# Tester.net
KiCad netlist of a schematic drawn in EAGLE
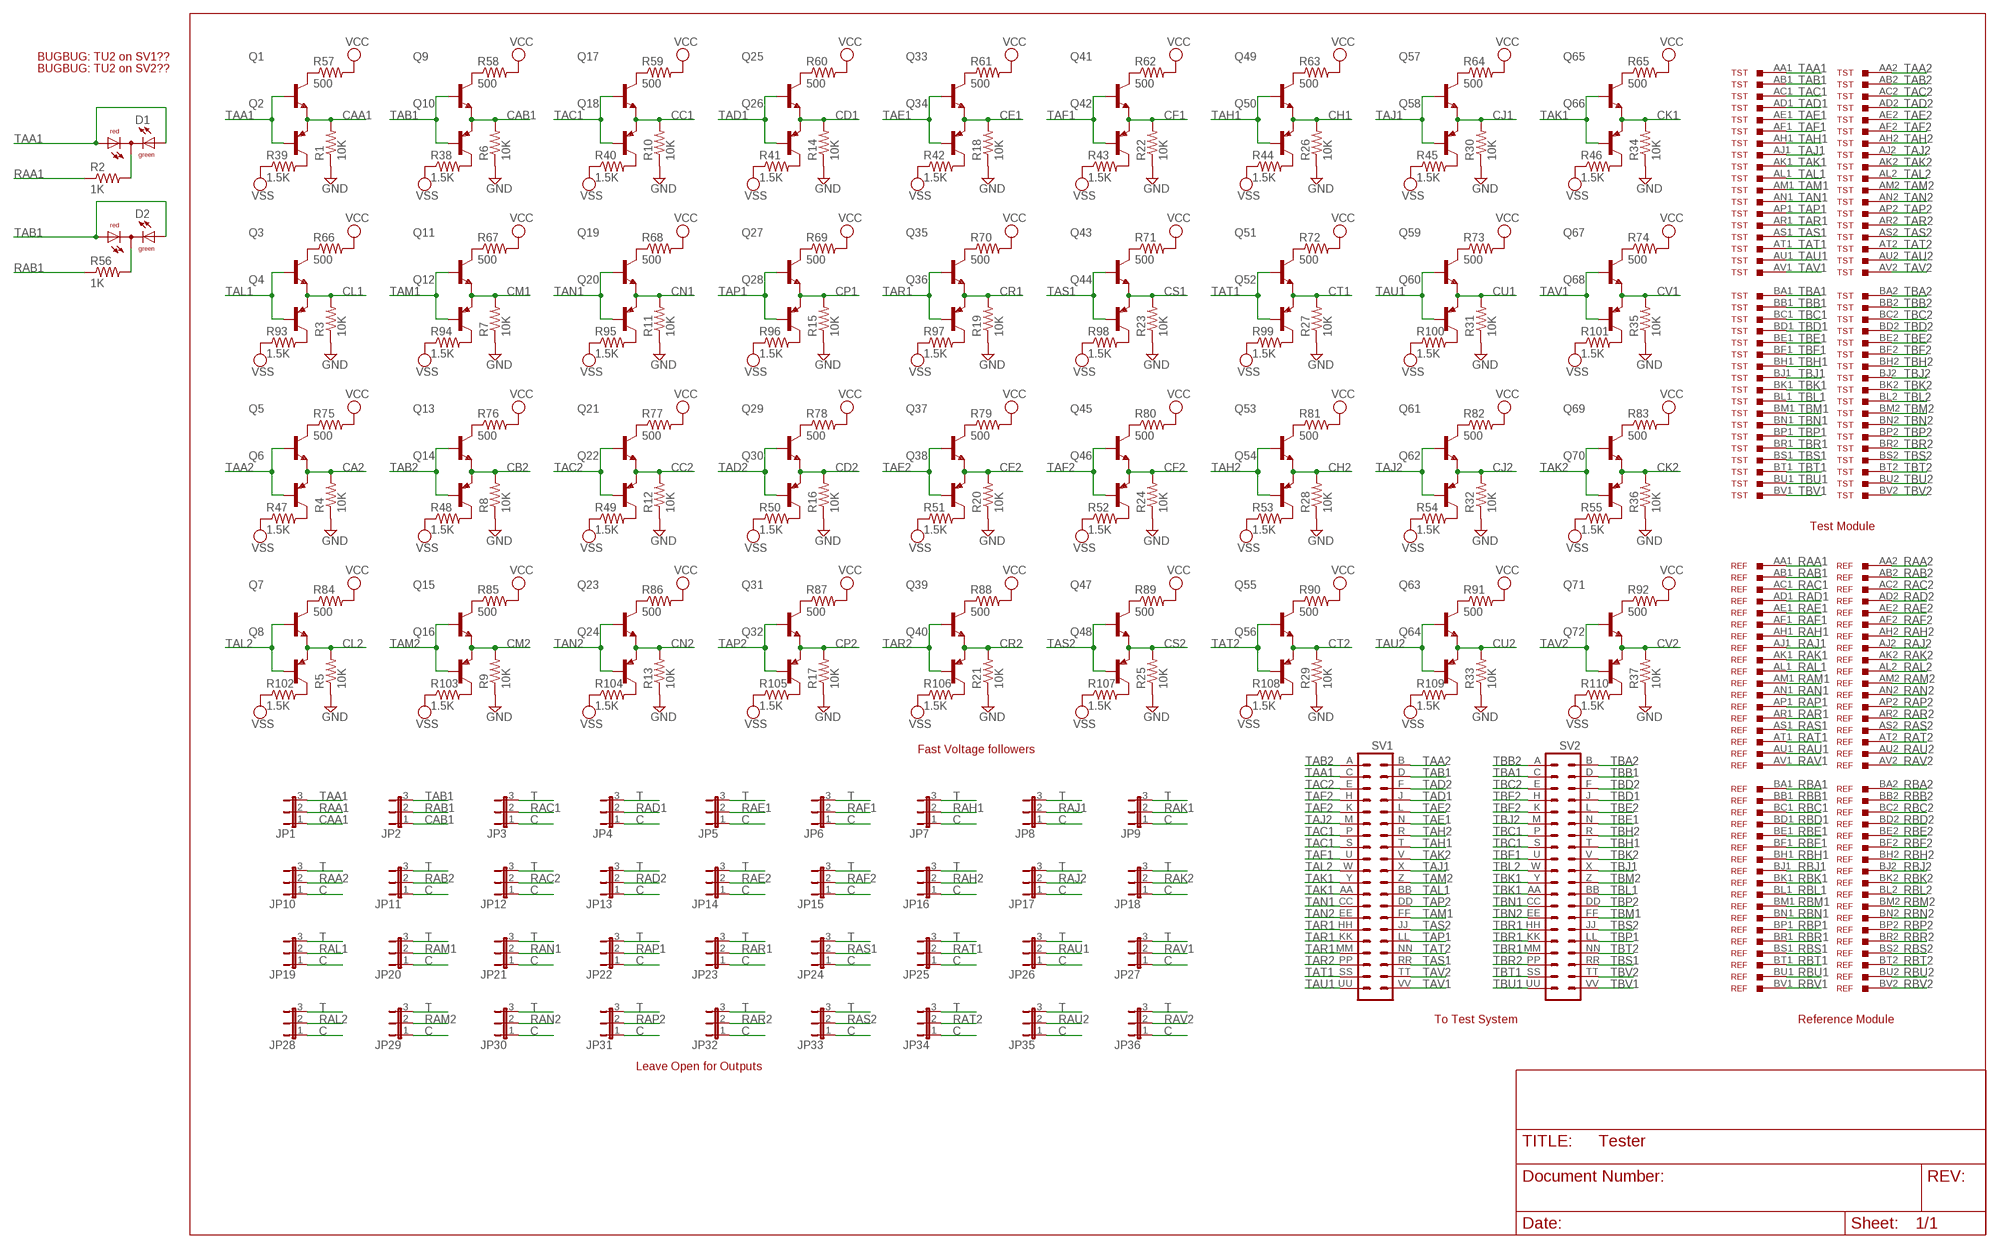
[diagram p0: schematic, sheet 1]

(export (version "E")
  (design (tool "Eeschema 10.0.6"))
  (components
    (comp (ref "D1")
      (value "DUOLED5MM")
      (footprint "eagle-import:DUOLED5MM")
      (libsource (lib "eagle-import") (part "DUOLED5MM"))
    )
    (comp (ref "D2")
      (value "DUOLED5MM")
      (footprint "eagle-import:DUOLED5MM")
      (libsource (lib "eagle-import") (part "DUOLED5MM"))
    )
    (comp (ref "JP1")
      (value "JP2E")
      (footprint "eagle-import:JP2")
      (libsource (lib "eagle-import") (part "JP2E"))
    )
    (comp (ref "JP2")
      (value "JP2E")
      (footprint "eagle-import:JP2")
      (libsource (lib "eagle-import") (part "JP2E"))
    )
    (comp (ref "JP3")
      (value "JP2E")
      (footprint "eagle-import:JP2")
      (libsource (lib "eagle-import") (part "JP2E"))
    )
    (comp (ref "JP4")
      (value "JP2E")
      (footprint "eagle-import:JP2")
      (libsource (lib "eagle-import") (part "JP2E"))
    )
    (comp (ref "JP5")
      (value "JP2E")
      (footprint "eagle-import:JP2")
      (libsource (lib "eagle-import") (part "JP2E"))
    )
    (comp (ref "JP6")
      (value "JP2E")
      (footprint "eagle-import:JP2")
      (libsource (lib "eagle-import") (part "JP2E"))
    )
    (comp (ref "JP7")
      (value "JP2E")
      (footprint "eagle-import:JP2")
      (libsource (lib "eagle-import") (part "JP2E"))
    )
    (comp (ref "JP8")
      (value "JP2E")
      (footprint "eagle-import:JP2")
      (libsource (lib "eagle-import") (part "JP2E"))
    )
    (comp (ref "JP9")
      (value "JP2E")
      (footprint "eagle-import:JP2")
      (libsource (lib "eagle-import") (part "JP2E"))
    )
    (comp (ref "JP10")
      (value "JP2E")
      (footprint "eagle-import:JP2")
      (libsource (lib "eagle-import") (part "JP2E"))
    )
    (comp (ref "JP11")
      (value "JP2E")
      (footprint "eagle-import:JP2")
      (libsource (lib "eagle-import") (part "JP2E"))
    )
    (comp (ref "JP12")
      (value "JP2E")
      (footprint "eagle-import:JP2")
      (libsource (lib "eagle-import") (part "JP2E"))
    )
    (comp (ref "JP13")
      (value "JP2E")
      (footprint "eagle-import:JP2")
      (libsource (lib "eagle-import") (part "JP2E"))
    )
    (comp (ref "JP14")
      (value "JP2E")
      (footprint "eagle-import:JP2")
      (libsource (lib "eagle-import") (part "JP2E"))
    )
    (comp (ref "JP15")
      (value "JP2E")
      (footprint "eagle-import:JP2")
      (libsource (lib "eagle-import") (part "JP2E"))
    )
    (comp (ref "JP16")
      (value "JP2E")
      (footprint "eagle-import:JP2")
      (libsource (lib "eagle-import") (part "JP2E"))
    )
    (comp (ref "JP17")
      (value "JP2E")
      (footprint "eagle-import:JP2")
      (libsource (lib "eagle-import") (part "JP2E"))
    )
    (comp (ref "JP18")
      (value "JP2E")
      (footprint "eagle-import:JP2")
      (libsource (lib "eagle-import") (part "JP2E"))
    )
    (comp (ref "JP19")
      (value "JP2E")
      (footprint "eagle-import:JP2")
      (libsource (lib "eagle-import") (part "JP2E"))
    )
    (comp (ref "JP20")
      (value "JP2E")
      (footprint "eagle-import:JP2")
      (libsource (lib "eagle-import") (part "JP2E"))
    )
    (comp (ref "JP21")
      (value "JP2E")
      (footprint "eagle-import:JP2")
      (libsource (lib "eagle-import") (part "JP2E"))
    )
    (comp (ref "JP22")
      (value "JP2E")
      (footprint "eagle-import:JP2")
      (libsource (lib "eagle-import") (part "JP2E"))
    )
    (comp (ref "JP23")
      (value "JP2E")
      (footprint "eagle-import:JP2")
      (libsource (lib "eagle-import") (part "JP2E"))
    )
    (comp (ref "JP24")
      (value "JP2E")
      (footprint "eagle-import:JP2")
      (libsource (lib "eagle-import") (part "JP2E"))
    )
    (comp (ref "JP25")
      (value "JP2E")
      (footprint "eagle-import:JP2")
      (libsource (lib "eagle-import") (part "JP2E"))
    )
    (comp (ref "JP26")
      (value "JP2E")
      (footprint "eagle-import:JP2")
      (libsource (lib "eagle-import") (part "JP2E"))
    )
    (comp (ref "JP27")
      (value "JP2E")
      (footprint "eagle-import:JP2")
      (libsource (lib "eagle-import") (part "JP2E"))
    )
    (comp (ref "JP28")
      (value "JP2E")
      (footprint "eagle-import:JP2")
      (libsource (lib "eagle-import") (part "JP2E"))
    )
    (comp (ref "JP29")
      (value "JP2E")
      (footprint "eagle-import:JP2")
      (libsource (lib "eagle-import") (part "JP2E"))
    )
    (comp (ref "JP30")
      (value "JP2E")
      (footprint "eagle-import:JP2")
      (libsource (lib "eagle-import") (part "JP2E"))
    )
    (comp (ref "JP31")
      (value "JP2E")
      (footprint "eagle-import:JP2")
      (libsource (lib "eagle-import") (part "JP2E"))
    )
    (comp (ref "JP32")
      (value "JP2E")
      (footprint "eagle-import:JP2")
      (libsource (lib "eagle-import") (part "JP2E"))
    )
    (comp (ref "JP33")
      (value "JP2E")
      (footprint "eagle-import:JP2")
      (libsource (lib "eagle-import") (part "JP2E"))
    )
    (comp (ref "JP34")
      (value "JP2E")
      (footprint "eagle-import:JP2")
      (libsource (lib "eagle-import") (part "JP2E"))
    )
    (comp (ref "JP35")
      (value "JP2E")
      (footprint "eagle-import:JP2")
      (libsource (lib "eagle-import") (part "JP2E"))
    )
    (comp (ref "JP36")
      (value "JP2E")
      (footprint "eagle-import:JP2")
      (libsource (lib "eagle-import") (part "JP2E"))
    )
    (comp (ref "Q1")
      (value "-NPN-TO5")
      (footprint "eagle-import:TO5")
      (libsource (lib "eagle-import") (part "-NPN-TO5"))
    )
    (comp (ref "Q2")
      (value "-PNP-TO5")
      (footprint "eagle-import:TO5")
      (libsource (lib "eagle-import") (part "-PNP-TO5"))
    )
    (comp (ref "Q3")
      (value "-NPN-TO5")
      (footprint "eagle-import:TO5")
      (libsource (lib "eagle-import") (part "-NPN-TO5"))
    )
    (comp (ref "Q4")
      (value "-PNP-TO5")
      (footprint "eagle-import:TO5")
      (libsource (lib "eagle-import") (part "-PNP-TO5"))
    )
    (comp (ref "Q5")
      (value "-NPN-TO5")
      (footprint "eagle-import:TO5")
      (libsource (lib "eagle-import") (part "-NPN-TO5"))
    )
    (comp (ref "Q6")
      (value "-PNP-TO5")
      (footprint "eagle-import:TO5")
      (libsource (lib "eagle-import") (part "-PNP-TO5"))
    )
    (comp (ref "Q7")
      (value "-NPN-TO5")
      (footprint "eagle-import:TO5")
      (libsource (lib "eagle-import") (part "-NPN-TO5"))
    )
    (comp (ref "Q8")
      (value "-PNP-TO5")
      (footprint "eagle-import:TO5")
      (libsource (lib "eagle-import") (part "-PNP-TO5"))
    )
    (comp (ref "Q9")
      (value "-NPN-TO5")
      (footprint "eagle-import:TO5")
      (libsource (lib "eagle-import") (part "-NPN-TO5"))
    )
    (comp (ref "Q10")
      (value "-PNP-TO5")
      (footprint "eagle-import:TO5")
      (libsource (lib "eagle-import") (part "-PNP-TO5"))
    )
    (comp (ref "Q11")
      (value "-NPN-TO5")
      (footprint "eagle-import:TO5")
      (libsource (lib "eagle-import") (part "-NPN-TO5"))
    )
    (comp (ref "Q12")
      (value "-PNP-TO5")
      (footprint "eagle-import:TO5")
      (libsource (lib "eagle-import") (part "-PNP-TO5"))
    )
    (comp (ref "Q13")
      (value "-NPN-TO5")
      (footprint "eagle-import:TO5")
      (libsource (lib "eagle-import") (part "-NPN-TO5"))
    )
    (comp (ref "Q14")
      (value "-PNP-TO5")
      (footprint "eagle-import:TO5")
      (libsource (lib "eagle-import") (part "-PNP-TO5"))
    )
    (comp (ref "Q15")
      (value "-NPN-TO5")
      (footprint "eagle-import:TO5")
      (libsource (lib "eagle-import") (part "-NPN-TO5"))
    )
    (comp (ref "Q16")
      (value "-PNP-TO5")
      (footprint "eagle-import:TO5")
      (libsource (lib "eagle-import") (part "-PNP-TO5"))
    )
    (comp (ref "Q17")
      (value "-NPN-TO5")
      (footprint "eagle-import:TO5")
      (libsource (lib "eagle-import") (part "-NPN-TO5"))
    )
    (comp (ref "Q18")
      (value "-PNP-TO5")
      (footprint "eagle-import:TO5")
      (libsource (lib "eagle-import") (part "-PNP-TO5"))
    )
    (comp (ref "Q19")
      (value "-NPN-TO5")
      (footprint "eagle-import:TO5")
      (libsource (lib "eagle-import") (part "-NPN-TO5"))
    )
    (comp (ref "Q20")
      (value "-PNP-TO5")
      (footprint "eagle-import:TO5")
      (libsource (lib "eagle-import") (part "-PNP-TO5"))
    )
    (comp (ref "Q21")
      (value "-NPN-TO5")
      (footprint "eagle-import:TO5")
      (libsource (lib "eagle-import") (part "-NPN-TO5"))
    )
    (comp (ref "Q22")
      (value "-PNP-TO5")
      (footprint "eagle-import:TO5")
      (libsource (lib "eagle-import") (part "-PNP-TO5"))
    )
    (comp (ref "Q23")
      (value "-NPN-TO5")
      (footprint "eagle-import:TO5")
      (libsource (lib "eagle-import") (part "-NPN-TO5"))
    )
    (comp (ref "Q24")
      (value "-PNP-TO5")
      (footprint "eagle-import:TO5")
      (libsource (lib "eagle-import") (part "-PNP-TO5"))
    )
    (comp (ref "Q25")
      (value "-NPN-TO5")
      (footprint "eagle-import:TO5")
      (libsource (lib "eagle-import") (part "-NPN-TO5"))
    )
    (comp (ref "Q26")
      (value "-PNP-TO5")
      (footprint "eagle-import:TO5")
      (libsource (lib "eagle-import") (part "-PNP-TO5"))
    )
    (comp (ref "Q27")
      (value "-NPN-TO5")
      (footprint "eagle-import:TO5")
      (libsource (lib "eagle-import") (part "-NPN-TO5"))
    )
    (comp (ref "Q28")
      (value "-PNP-TO5")
      (footprint "eagle-import:TO5")
      (libsource (lib "eagle-import") (part "-PNP-TO5"))
    )
    (comp (ref "Q29")
      (value "-NPN-TO5")
      (footprint "eagle-import:TO5")
      (libsource (lib "eagle-import") (part "-NPN-TO5"))
    )
    (comp (ref "Q30")
      (value "-PNP-TO5")
      (footprint "eagle-import:TO5")
      (libsource (lib "eagle-import") (part "-PNP-TO5"))
    )
    (comp (ref "Q31")
      (value "-NPN-TO5")
      (footprint "eagle-import:TO5")
      (libsource (lib "eagle-import") (part "-NPN-TO5"))
    )
    (comp (ref "Q32")
      (value "-PNP-TO5")
      (footprint "eagle-import:TO5")
      (libsource (lib "eagle-import") (part "-PNP-TO5"))
    )
    (comp (ref "Q33")
      (value "-NPN-TO5")
      (footprint "eagle-import:TO5")
      (libsource (lib "eagle-import") (part "-NPN-TO5"))
    )
    (comp (ref "Q34")
      (value "-PNP-TO5")
      (footprint "eagle-import:TO5")
      (libsource (lib "eagle-import") (part "-PNP-TO5"))
    )
    (comp (ref "Q35")
      (value "-NPN-TO5")
      (footprint "eagle-import:TO5")
      (libsource (lib "eagle-import") (part "-NPN-TO5"))
    )
    (comp (ref "Q36")
      (value "-PNP-TO5")
      (footprint "eagle-import:TO5")
      (libsource (lib "eagle-import") (part "-PNP-TO5"))
    )
    (comp (ref "Q37")
      (value "-NPN-TO5")
      (footprint "eagle-import:TO5")
      (libsource (lib "eagle-import") (part "-NPN-TO5"))
    )
    (comp (ref "Q38")
      (value "-PNP-TO5")
      (footprint "eagle-import:TO5")
      (libsource (lib "eagle-import") (part "-PNP-TO5"))
    )
    (comp (ref "Q39")
      (value "-NPN-TO5")
      (footprint "eagle-import:TO5")
      (libsource (lib "eagle-import") (part "-NPN-TO5"))
    )
    (comp (ref "Q40")
      (value "-PNP-TO5")
      (footprint "eagle-import:TO5")
      (libsource (lib "eagle-import") (part "-PNP-TO5"))
    )
    (comp (ref "Q41")
      (value "-NPN-TO5")
      (footprint "eagle-import:TO5")
      (libsource (lib "eagle-import") (part "-NPN-TO5"))
    )
    (comp (ref "Q42")
      (value "-PNP-TO5")
      (footprint "eagle-import:TO5")
      (libsource (lib "eagle-import") (part "-PNP-TO5"))
    )
    (comp (ref "Q43")
      (value "-NPN-TO5")
      (footprint "eagle-import:TO5")
      (libsource (lib "eagle-import") (part "-NPN-TO5"))
    )
    (comp (ref "Q44")
      (value "-PNP-TO5")
      (footprint "eagle-import:TO5")
      (libsource (lib "eagle-import") (part "-PNP-TO5"))
    )
    (comp (ref "Q45")
      (value "-NPN-TO5")
      (footprint "eagle-import:TO5")
      (libsource (lib "eagle-import") (part "-NPN-TO5"))
    )
    (comp (ref "Q46")
      (value "-PNP-TO5")
      (footprint "eagle-import:TO5")
      (libsource (lib "eagle-import") (part "-PNP-TO5"))
    )
    (comp (ref "Q47")
      (value "-NPN-TO5")
      (footprint "eagle-import:TO5")
      (libsource (lib "eagle-import") (part "-NPN-TO5"))
    )
    (comp (ref "Q48")
      (value "-PNP-TO5")
      (footprint "eagle-import:TO5")
      (libsource (lib "eagle-import") (part "-PNP-TO5"))
    )
    (comp (ref "Q49")
      (value "-NPN-TO5")
      (footprint "eagle-import:TO5")
      (libsource (lib "eagle-import") (part "-NPN-TO5"))
    )
    (comp (ref "Q50")
      (value "-PNP-TO5")
      (footprint "eagle-import:TO5")
      (libsource (lib "eagle-import") (part "-PNP-TO5"))
    )
    (comp (ref "Q51")
      (value "-NPN-TO5")
      (footprint "eagle-import:TO5")
      (libsource (lib "eagle-import") (part "-NPN-TO5"))
    )
    (comp (ref "Q52")
      (value "-PNP-TO5")
      (footprint "eagle-import:TO5")
      (libsource (lib "eagle-import") (part "-PNP-TO5"))
    )
    (comp (ref "Q53")
      (value "-NPN-TO5")
      (footprint "eagle-import:TO5")
      (libsource (lib "eagle-import") (part "-NPN-TO5"))
    )
    (comp (ref "Q54")
      (value "-PNP-TO5")
      (footprint "eagle-import:TO5")
      (libsource (lib "eagle-import") (part "-PNP-TO5"))
    )
    (comp (ref "Q55")
      (value "-NPN-TO5")
      (footprint "eagle-import:TO5")
      (libsource (lib "eagle-import") (part "-NPN-TO5"))
    )
    (comp (ref "Q56")
      (value "-PNP-TO5")
      (footprint "eagle-import:TO5")
      (libsource (lib "eagle-import") (part "-PNP-TO5"))
    )
    (comp (ref "Q57")
      (value "-NPN-TO5")
      (footprint "eagle-import:TO5")
      (libsource (lib "eagle-import") (part "-NPN-TO5"))
    )
    (comp (ref "Q58")
      (value "-PNP-TO5")
      (footprint "eagle-import:TO5")
      (libsource (lib "eagle-import") (part "-PNP-TO5"))
    )
    (comp (ref "Q59")
      (value "-NPN-TO5")
      (footprint "eagle-import:TO5")
      (libsource (lib "eagle-import") (part "-NPN-TO5"))
    )
    (comp (ref "Q60")
      (value "-PNP-TO5")
      (footprint "eagle-import:TO5")
      (libsource (lib "eagle-import") (part "-PNP-TO5"))
    )
    (comp (ref "Q61")
      (value "-NPN-TO5")
      (footprint "eagle-import:TO5")
      (libsource (lib "eagle-import") (part "-NPN-TO5"))
    )
    (comp (ref "Q62")
      (value "-PNP-TO5")
      (footprint "eagle-import:TO5")
      (libsource (lib "eagle-import") (part "-PNP-TO5"))
    )
    (comp (ref "Q63")
      (value "-NPN-TO5")
      (footprint "eagle-import:TO5")
      (libsource (lib "eagle-import") (part "-NPN-TO5"))
    )
    (comp (ref "Q64")
      (value "-PNP-TO5")
      (footprint "eagle-import:TO5")
      (libsource (lib "eagle-import") (part "-PNP-TO5"))
    )
    (comp (ref "Q65")
      (value "-NPN-TO5")
      (footprint "eagle-import:TO5")
      (libsource (lib "eagle-import") (part "-NPN-TO5"))
    )
    (comp (ref "Q66")
      (value "-PNP-TO5")
      (footprint "eagle-import:TO5")
      (libsource (lib "eagle-import") (part "-PNP-TO5"))
    )
    (comp (ref "Q67")
      (value "-NPN-TO5")
      (footprint "eagle-import:TO5")
      (libsource (lib "eagle-import") (part "-NPN-TO5"))
    )
    (comp (ref "Q68")
      (value "-PNP-TO5")
      (footprint "eagle-import:TO5")
      (libsource (lib "eagle-import") (part "-PNP-TO5"))
    )
    (comp (ref "Q69")
      (value "-NPN-TO5")
      (footprint "eagle-import:TO5")
      (libsource (lib "eagle-import") (part "-NPN-TO5"))
    )
    (comp (ref "Q70")
      (value "-PNP-TO5")
      (footprint "eagle-import:TO5")
      (libsource (lib "eagle-import") (part "-PNP-TO5"))
    )
    (comp (ref "Q71")
      (value "-NPN-TO5")
      (footprint "eagle-import:TO5")
      (libsource (lib "eagle-import") (part "-NPN-TO5"))
    )
    (comp (ref "Q72")
      (value "-PNP-TO5")
      (footprint "eagle-import:TO5")
      (libsource (lib "eagle-import") (part "-PNP-TO5"))
    )
    (comp (ref "R1")
      (value "10K")
      (footprint "eagle-import:0207_10")
      (libsource (lib "eagle-import") (part "R-US_0207/10"))
    )
    (comp (ref "R2")
      (value "1K")
      (footprint "eagle-import:0207_10")
      (libsource (lib "eagle-import") (part "R-US_0207/10"))
    )
    (comp (ref "R3")
      (value "10K")
      (footprint "eagle-import:0207_10")
      (libsource (lib "eagle-import") (part "R-US_0207/10"))
    )
    (comp (ref "R4")
      (value "10K")
      (footprint "eagle-import:0207_10")
      (libsource (lib "eagle-import") (part "R-US_0207/10"))
    )
    (comp (ref "R5")
      (value "10K")
      (footprint "eagle-import:0207_10")
      (libsource (lib "eagle-import") (part "R-US_0207/10"))
    )
    (comp (ref "R6")
      (value "10K")
      (footprint "eagle-import:0207_10")
      (libsource (lib "eagle-import") (part "R-US_0207/10"))
    )
    (comp (ref "R7")
      (value "10K")
      (footprint "eagle-import:0207_10")
      (libsource (lib "eagle-import") (part "R-US_0207/10"))
    )
    (comp (ref "R8")
      (value "10K")
      (footprint "eagle-import:0207_10")
      (libsource (lib "eagle-import") (part "R-US_0207/10"))
    )
    (comp (ref "R9")
      (value "10K")
      (footprint "eagle-import:0207_10")
      (libsource (lib "eagle-import") (part "R-US_0207/10"))
    )
    (comp (ref "R10")
      (value "10K")
      (footprint "eagle-import:0207_10")
      (libsource (lib "eagle-import") (part "R-US_0207/10"))
    )
    (comp (ref "R11")
      (value "10K")
      (footprint "eagle-import:0207_10")
      (libsource (lib "eagle-import") (part "R-US_0207/10"))
    )
    (comp (ref "R12")
      (value "10K")
      (footprint "eagle-import:0207_10")
      (libsource (lib "eagle-import") (part "R-US_0207/10"))
    )
    (comp (ref "R13")
      (value "10K")
      (footprint "eagle-import:0207_10")
      (libsource (lib "eagle-import") (part "R-US_0207/10"))
    )
    (comp (ref "R14")
      (value "10K")
      (footprint "eagle-import:0207_10")
      (libsource (lib "eagle-import") (part "R-US_0207/10"))
    )
    (comp (ref "R15")
      (value "10K")
      (footprint "eagle-import:0207_10")
      (libsource (lib "eagle-import") (part "R-US_0207/10"))
    )
    (comp (ref "R16")
      (value "10K")
      (footprint "eagle-import:0207_10")
      (libsource (lib "eagle-import") (part "R-US_0207/10"))
    )
    (comp (ref "R17")
      (value "10K")
      (footprint "eagle-import:0207_10")
      (libsource (lib "eagle-import") (part "R-US_0207/10"))
    )
    (comp (ref "R18")
      (value "10K")
      (footprint "eagle-import:0207_10")
      (libsource (lib "eagle-import") (part "R-US_0207/10"))
    )
    (comp (ref "R19")
      (value "10K")
      (footprint "eagle-import:0207_10")
      (libsource (lib "eagle-import") (part "R-US_0207/10"))
    )
    (comp (ref "R20")
      (value "10K")
      (footprint "eagle-import:0207_10")
      (libsource (lib "eagle-import") (part "R-US_0207/10"))
    )
    (comp (ref "R21")
      (value "10K")
      (footprint "eagle-import:0207_10")
      (libsource (lib "eagle-import") (part "R-US_0207/10"))
    )
    (comp (ref "R22")
      (value "10K")
      (footprint "eagle-import:0207_10")
      (libsource (lib "eagle-import") (part "R-US_0207/10"))
    )
    (comp (ref "R23")
      (value "10K")
      (footprint "eagle-import:0207_10")
      (libsource (lib "eagle-import") (part "R-US_0207/10"))
    )
    (comp (ref "R24")
      (value "10K")
      (footprint "eagle-import:0207_10")
      (libsource (lib "eagle-import") (part "R-US_0207/10"))
    )
    (comp (ref "R25")
      (value "10K")
      (footprint "eagle-import:0207_10")
      (libsource (lib "eagle-import") (part "R-US_0207/10"))
    )
    (comp (ref "R26")
      (value "10K")
      (footprint "eagle-import:0207_10")
      (libsource (lib "eagle-import") (part "R-US_0207/10"))
    )
    (comp (ref "R27")
      (value "10K")
      (footprint "eagle-import:0207_10")
      (libsource (lib "eagle-import") (part "R-US_0207/10"))
    )
    (comp (ref "R28")
      (value "10K")
      (footprint "eagle-import:0207_10")
      (libsource (lib "eagle-import") (part "R-US_0207/10"))
    )
    (comp (ref "R29")
      (value "10K")
      (footprint "eagle-import:0207_10")
      (libsource (lib "eagle-import") (part "R-US_0207/10"))
    )
    (comp (ref "R30")
      (value "10K")
      (footprint "eagle-import:0207_10")
      (libsource (lib "eagle-import") (part "R-US_0207/10"))
    )
    (comp (ref "R31")
      (value "10K")
      (footprint "eagle-import:0207_10")
      (libsource (lib "eagle-import") (part "R-US_0207/10"))
    )
    (comp (ref "R32")
      (value "10K")
      (footprint "eagle-import:0207_10")
      (libsource (lib "eagle-import") (part "R-US_0207/10"))
    )
    (comp (ref "R33")
      (value "10K")
      (footprint "eagle-import:0207_10")
      (libsource (lib "eagle-import") (part "R-US_0207/10"))
    )
    (comp (ref "R34")
      (value "10K")
      (footprint "eagle-import:0207_10")
      (libsource (lib "eagle-import") (part "R-US_0207/10"))
    )
    (comp (ref "R35")
      (value "10K")
      (footprint "eagle-import:0207_10")
      (libsource (lib "eagle-import") (part "R-US_0207/10"))
    )
    (comp (ref "R36")
      (value "10K")
      (footprint "eagle-import:0207_10")
      (libsource (lib "eagle-import") (part "R-US_0207/10"))
    )
    (comp (ref "R37")
      (value "10K")
      (footprint "eagle-import:0207_10")
      (libsource (lib "eagle-import") (part "R-US_0207/10"))
    )
    (comp (ref "R38")
      (value "1.5K")
      (footprint "eagle-import:0207_10")
      (libsource (lib "eagle-import") (part "R-US_0207/10"))
    )
    (comp (ref "R39")
      (value "1.5K")
      (footprint "eagle-import:0207_10")
      (libsource (lib "eagle-import") (part "R-US_0207/10"))
    )
    (comp (ref "R40")
      (value "1.5K")
      (footprint "eagle-import:0207_10")
      (libsource (lib "eagle-import") (part "R-US_0207/10"))
    )
    (comp (ref "R41")
      (value "1.5K")
      (footprint "eagle-import:0207_10")
      (libsource (lib "eagle-import") (part "R-US_0207/10"))
    )
    (comp (ref "R42")
      (value "1.5K")
      (footprint "eagle-import:0207_10")
      (libsource (lib "eagle-import") (part "R-US_0207/10"))
    )
    (comp (ref "R43")
      (value "1.5K")
      (footprint "eagle-import:0207_10")
      (libsource (lib "eagle-import") (part "R-US_0207/10"))
    )
    (comp (ref "R44")
      (value "1.5K")
      (footprint "eagle-import:0207_10")
      (libsource (lib "eagle-import") (part "R-US_0207/10"))
    )
    (comp (ref "R45")
      (value "1.5K")
      (footprint "eagle-import:0207_10")
      (libsource (lib "eagle-import") (part "R-US_0207/10"))
    )
    (comp (ref "R46")
      (value "1.5K")
      (footprint "eagle-import:0207_10")
      (libsource (lib "eagle-import") (part "R-US_0207/10"))
    )
    (comp (ref "R47")
      (value "1.5K")
      (footprint "eagle-import:0207_10")
      (libsource (lib "eagle-import") (part "R-US_0207/10"))
    )
    (comp (ref "R48")
      (value "1.5K")
      (footprint "eagle-import:0207_10")
      (libsource (lib "eagle-import") (part "R-US_0207/10"))
    )
    (comp (ref "R49")
      (value "1.5K")
      (footprint "eagle-import:0207_10")
      (libsource (lib "eagle-import") (part "R-US_0207/10"))
    )
    (comp (ref "R50")
      (value "1.5K")
      (footprint "eagle-import:0207_10")
      (libsource (lib "eagle-import") (part "R-US_0207/10"))
    )
    (comp (ref "R51")
      (value "1.5K")
      (footprint "eagle-import:0207_10")
      (libsource (lib "eagle-import") (part "R-US_0207/10"))
    )
    (comp (ref "R52")
      (value "1.5K")
      (footprint "eagle-import:0207_10")
      (libsource (lib "eagle-import") (part "R-US_0207/10"))
    )
    (comp (ref "R53")
      (value "1.5K")
      (footprint "eagle-import:0207_10")
      (libsource (lib "eagle-import") (part "R-US_0207/10"))
    )
    (comp (ref "R54")
      (value "1.5K")
      (footprint "eagle-import:0207_10")
      (libsource (lib "eagle-import") (part "R-US_0207/10"))
    )
    (comp (ref "R55")
      (value "1.5K")
      (footprint "eagle-import:0207_10")
      (libsource (lib "eagle-import") (part "R-US_0207/10"))
    )
    (comp (ref "R56")
      (value "1K")
      (footprint "eagle-import:0207_10")
      (libsource (lib "eagle-import") (part "R-US_0207/10"))
    )
    (comp (ref "R57")
      (value "500")
      (footprint "eagle-import:0207_10")
      (libsource (lib "eagle-import") (part "R-US_0207/10"))
    )
    (comp (ref "R58")
      (value "500")
      (footprint "eagle-import:0207_10")
      (libsource (lib "eagle-import") (part "R-US_0207/10"))
    )
    (comp (ref "R59")
      (value "500")
      (footprint "eagle-import:0207_10")
      (libsource (lib "eagle-import") (part "R-US_0207/10"))
    )
    (comp (ref "R60")
      (value "500")
      (footprint "eagle-import:0207_10")
      (libsource (lib "eagle-import") (part "R-US_0207/10"))
    )
    (comp (ref "R61")
      (value "500")
      (footprint "eagle-import:0207_10")
      (libsource (lib "eagle-import") (part "R-US_0207/10"))
    )
    (comp (ref "R62")
      (value "500")
      (footprint "eagle-import:0207_10")
      (libsource (lib "eagle-import") (part "R-US_0207/10"))
    )
    (comp (ref "R63")
      (value "500")
      (footprint "eagle-import:0207_10")
      (libsource (lib "eagle-import") (part "R-US_0207/10"))
    )
    (comp (ref "R64")
      (value "500")
      (footprint "eagle-import:0207_10")
      (libsource (lib "eagle-import") (part "R-US_0207/10"))
    )
    (comp (ref "R65")
      (value "500")
      (footprint "eagle-import:0207_10")
      (libsource (lib "eagle-import") (part "R-US_0207/10"))
    )
    (comp (ref "R66")
      (value "500")
      (footprint "eagle-import:0207_10")
      (libsource (lib "eagle-import") (part "R-US_0207/10"))
    )
    (comp (ref "R67")
      (value "500")
      (footprint "eagle-import:0207_10")
      (libsource (lib "eagle-import") (part "R-US_0207/10"))
    )
    (comp (ref "R68")
      (value "500")
      (footprint "eagle-import:0207_10")
      (libsource (lib "eagle-import") (part "R-US_0207/10"))
    )
    (comp (ref "R69")
      (value "500")
      (footprint "eagle-import:0207_10")
      (libsource (lib "eagle-import") (part "R-US_0207/10"))
    )
    (comp (ref "R70")
      (value "500")
      (footprint "eagle-import:0207_10")
      (libsource (lib "eagle-import") (part "R-US_0207/10"))
    )
    (comp (ref "R71")
      (value "500")
      (footprint "eagle-import:0207_10")
      (libsource (lib "eagle-import") (part "R-US_0207/10"))
    )
    (comp (ref "R72")
      (value "500")
      (footprint "eagle-import:0207_10")
      (libsource (lib "eagle-import") (part "R-US_0207/10"))
    )
    (comp (ref "R73")
      (value "500")
      (footprint "eagle-import:0207_10")
      (libsource (lib "eagle-import") (part "R-US_0207/10"))
    )
    (comp (ref "R74")
      (value "500")
      (footprint "eagle-import:0207_10")
      (libsource (lib "eagle-import") (part "R-US_0207/10"))
    )
    (comp (ref "R75")
      (value "500")
      (footprint "eagle-import:0207_10")
      (libsource (lib "eagle-import") (part "R-US_0207/10"))
    )
    (comp (ref "R76")
      (value "500")
      (footprint "eagle-import:0207_10")
      (libsource (lib "eagle-import") (part "R-US_0207/10"))
    )
    (comp (ref "R77")
      (value "500")
      (footprint "eagle-import:0207_10")
      (libsource (lib "eagle-import") (part "R-US_0207/10"))
    )
    (comp (ref "R78")
      (value "500")
      (footprint "eagle-import:0207_10")
      (libsource (lib "eagle-import") (part "R-US_0207/10"))
    )
    (comp (ref "R79")
      (value "500")
      (footprint "eagle-import:0207_10")
      (libsource (lib "eagle-import") (part "R-US_0207/10"))
    )
    (comp (ref "R80")
      (value "500")
      (footprint "eagle-import:0207_10")
      (libsource (lib "eagle-import") (part "R-US_0207/10"))
    )
    (comp (ref "R81")
      (value "500")
      (footprint "eagle-import:0207_10")
      (libsource (lib "eagle-import") (part "R-US_0207/10"))
    )
    (comp (ref "R82")
      (value "500")
      (footprint "eagle-import:0207_10")
      (libsource (lib "eagle-import") (part "R-US_0207/10"))
    )
    (comp (ref "R83")
      (value "500")
      (footprint "eagle-import:0207_10")
      (libsource (lib "eagle-import") (part "R-US_0207/10"))
    )
    (comp (ref "R84")
      (value "500")
      (footprint "eagle-import:0207_10")
      (libsource (lib "eagle-import") (part "R-US_0207/10"))
    )
    (comp (ref "R85")
      (value "500")
      (footprint "eagle-import:0207_10")
      (libsource (lib "eagle-import") (part "R-US_0207/10"))
    )
    (comp (ref "R86")
      (value "500")
      (footprint "eagle-import:0207_10")
      (libsource (lib "eagle-import") (part "R-US_0207/10"))
    )
    (comp (ref "R87")
      (value "500")
      (footprint "eagle-import:0207_10")
      (libsource (lib "eagle-import") (part "R-US_0207/10"))
    )
    (comp (ref "R88")
      (value "500")
      (footprint "eagle-import:0207_10")
      (libsource (lib "eagle-import") (part "R-US_0207/10"))
    )
    (comp (ref "R89")
      (value "500")
      (footprint "eagle-import:0207_10")
      (libsource (lib "eagle-import") (part "R-US_0207/10"))
    )
    (comp (ref "R90")
      (value "500")
      (footprint "eagle-import:0207_10")
      (libsource (lib "eagle-import") (part "R-US_0207/10"))
    )
    (comp (ref "R91")
      (value "500")
      (footprint "eagle-import:0207_10")
      (libsource (lib "eagle-import") (part "R-US_0207/10"))
    )
    (comp (ref "R92")
      (value "500")
      (footprint "eagle-import:0207_10")
      (libsource (lib "eagle-import") (part "R-US_0207/10"))
    )
    (comp (ref "R93")
      (value "1.5K")
      (footprint "eagle-import:0207_10")
      (libsource (lib "eagle-import") (part "R-US_0207/10"))
    )
    (comp (ref "R94")
      (value "1.5K")
      (footprint "eagle-import:0207_10")
      (libsource (lib "eagle-import") (part "R-US_0207/10"))
    )
    (comp (ref "R95")
      (value "1.5K")
      (footprint "eagle-import:0207_10")
      (libsource (lib "eagle-import") (part "R-US_0207/10"))
    )
    (comp (ref "R96")
      (value "1.5K")
      (footprint "eagle-import:0207_10")
      (libsource (lib "eagle-import") (part "R-US_0207/10"))
    )
    (comp (ref "R97")
      (value "1.5K")
      (footprint "eagle-import:0207_10")
      (libsource (lib "eagle-import") (part "R-US_0207/10"))
    )
    (comp (ref "R98")
      (value "1.5K")
      (footprint "eagle-import:0207_10")
      (libsource (lib "eagle-import") (part "R-US_0207/10"))
    )
    (comp (ref "R99")
      (value "1.5K")
      (footprint "eagle-import:0207_10")
      (libsource (lib "eagle-import") (part "R-US_0207/10"))
    )
    (comp (ref "R100")
      (value "1.5K")
      (footprint "eagle-import:0207_10")
      (libsource (lib "eagle-import") (part "R-US_0207/10"))
    )
    (comp (ref "R101")
      (value "1.5K")
      (footprint "eagle-import:0207_10")
      (libsource (lib "eagle-import") (part "R-US_0207/10"))
    )
    (comp (ref "R102")
      (value "1.5K")
      (footprint "eagle-import:0207_10")
      (libsource (lib "eagle-import") (part "R-US_0207/10"))
    )
    (comp (ref "R103")
      (value "1.5K")
      (footprint "eagle-import:0207_10")
      (libsource (lib "eagle-import") (part "R-US_0207/10"))
    )
    (comp (ref "R104")
      (value "1.5K")
      (footprint "eagle-import:0207_10")
      (libsource (lib "eagle-import") (part "R-US_0207/10"))
    )
    (comp (ref "R105")
      (value "1.5K")
      (footprint "eagle-import:0207_10")
      (libsource (lib "eagle-import") (part "R-US_0207/10"))
    )
    (comp (ref "R106")
      (value "1.5K")
      (footprint "eagle-import:0207_10")
      (libsource (lib "eagle-import") (part "R-US_0207/10"))
    )
    (comp (ref "R107")
      (value "1.5K")
      (footprint "eagle-import:0207_10")
      (libsource (lib "eagle-import") (part "R-US_0207/10"))
    )
    (comp (ref "R108")
      (value "1.5K")
      (footprint "eagle-import:0207_10")
      (libsource (lib "eagle-import") (part "R-US_0207/10"))
    )
    (comp (ref "R109")
      (value "1.5K")
      (footprint "eagle-import:0207_10")
      (libsource (lib "eagle-import") (part "R-US_0207/10"))
    )
    (comp (ref "R110")
      (value "1.5K")
      (footprint "eagle-import:0207_10")
      (libsource (lib "eagle-import") (part "R-US_0207/10"))
    )
    (comp (ref "REF")
      (value "W971")
      (footprint "eagle-import:H807-2")
      (libsource (lib "eagle-import") (part "W971"))
    )
    (comp (ref "SV1")
      (value "DEC40PINV")
      (footprint "eagle-import:DEC40PINV")
      (libsource (lib "eagle-import") (part "DEC40PINV"))
    )
    (comp (ref "SV2")
      (value "DEC40PINV")
      (footprint "eagle-import:DEC40PINV")
      (libsource (lib "eagle-import") (part "DEC40PINV"))
    )
    (comp (ref "TST")
      (value "W971")
      (footprint "eagle-import:H807-2")
      (libsource (lib "eagle-import") (part "W971"))
    )
  )
  (nets
    (net (code "1") (name "/C") (class "Default")
      (node (ref "JP10") (pin "1") (pinfunction "1_1") (pintype "passive"))
      (node (ref "JP11") (pin "1") (pinfunction "1_1") (pintype "passive"))
      (node (ref "JP12") (pin "1") (pinfunction "1_1") (pintype "passive"))
      (node (ref "JP13") (pin "1") (pinfunction "1_1") (pintype "passive"))
      (node (ref "JP14") (pin "1") (pinfunction "1_1") (pintype "passive"))
      (node (ref "JP15") (pin "1") (pinfunction "1_1") (pintype "passive"))
      (node (ref "JP16") (pin "1") (pinfunction "1_1") (pintype "passive"))
      (node (ref "JP17") (pin "1") (pinfunction "1_1") (pintype "passive"))
      (node (ref "JP18") (pin "1") (pinfunction "1_1") (pintype "passive"))
      (node (ref "JP19") (pin "1") (pinfunction "1_1") (pintype "passive"))
      (node (ref "JP20") (pin "1") (pinfunction "1_1") (pintype "passive"))
      (node (ref "JP21") (pin "1") (pinfunction "1_1") (pintype "passive"))
      (node (ref "JP22") (pin "1") (pinfunction "1_1") (pintype "passive"))
      (node (ref "JP23") (pin "1") (pinfunction "1_1") (pintype "passive"))
      (node (ref "JP24") (pin "1") (pinfunction "1_1") (pintype "passive"))
      (node (ref "JP25") (pin "1") (pinfunction "1_1") (pintype "passive"))
      (node (ref "JP26") (pin "1") (pinfunction "1_1") (pintype "passive"))
      (node (ref "JP27") (pin "1") (pinfunction "1_1") (pintype "passive"))
      (node (ref "JP28") (pin "1") (pinfunction "1_1") (pintype "passive"))
      (node (ref "JP29") (pin "1") (pinfunction "1_1") (pintype "passive"))
      (node (ref "JP3") (pin "1") (pinfunction "1_1") (pintype "passive"))
      (node (ref "JP30") (pin "1") (pinfunction "1_1") (pintype "passive"))
      (node (ref "JP31") (pin "1") (pinfunction "1_1") (pintype "passive"))
      (node (ref "JP32") (pin "1") (pinfunction "1_1") (pintype "passive"))
      (node (ref "JP33") (pin "1") (pinfunction "1_1") (pintype "passive"))
      (node (ref "JP34") (pin "1") (pinfunction "1_1") (pintype "passive"))
      (node (ref "JP35") (pin "1") (pinfunction "1_1") (pintype "passive"))
      (node (ref "JP36") (pin "1") (pinfunction "1_1") (pintype "passive"))
      (node (ref "JP4") (pin "1") (pinfunction "1_1") (pintype "passive"))
      (node (ref "JP5") (pin "1") (pinfunction "1_1") (pintype "passive"))
      (node (ref "JP6") (pin "1") (pinfunction "1_1") (pintype "passive"))
      (node (ref "JP7") (pin "1") (pinfunction "1_1") (pintype "passive"))
      (node (ref "JP8") (pin "1") (pinfunction "1_1") (pintype "passive"))
      (node (ref "JP9") (pin "1") (pinfunction "1_1") (pintype "passive"))
    )
    (net (code "2") (name "/CA2") (class "Default")
      (node (ref "Q5") (pin "1") (pinfunction "E_1") (pintype "passive"))
      (node (ref "Q6") (pin "1") (pinfunction "E_1") (pintype "passive"))
      (node (ref "R4") (pin "2") (pinfunction "2_2") (pintype "passive"))
    )
    (net (code "3") (name "/CAA1") (class "Default")
      (node (ref "JP1") (pin "1") (pinfunction "1_1") (pintype "passive"))
      (node (ref "Q1") (pin "1") (pinfunction "E_1") (pintype "passive"))
      (node (ref "Q2") (pin "1") (pinfunction "E_1") (pintype "passive"))
      (node (ref "R1") (pin "2") (pinfunction "2_2") (pintype "passive"))
    )
    (net (code "4") (name "/CAB1") (class "Default")
      (node (ref "JP2") (pin "1") (pinfunction "1_1") (pintype "passive"))
      (node (ref "Q10") (pin "1") (pinfunction "E_1") (pintype "passive"))
      (node (ref "Q9") (pin "1") (pinfunction "E_1") (pintype "passive"))
      (node (ref "R6") (pin "2") (pinfunction "2_2") (pintype "passive"))
    )
    (net (code "5") (name "/CB2") (class "Default")
      (node (ref "Q13") (pin "1") (pinfunction "E_1") (pintype "passive"))
      (node (ref "Q14") (pin "1") (pinfunction "E_1") (pintype "passive"))
      (node (ref "R8") (pin "2") (pinfunction "2_2") (pintype "passive"))
    )
    (net (code "6") (name "/CC1") (class "Default")
      (node (ref "Q17") (pin "1") (pinfunction "E_1") (pintype "passive"))
      (node (ref "Q18") (pin "1") (pinfunction "E_1") (pintype "passive"))
      (node (ref "R10") (pin "2") (pinfunction "2_2") (pintype "passive"))
    )
    (net (code "7") (name "/CC2") (class "Default")
      (node (ref "Q21") (pin "1") (pinfunction "E_1") (pintype "passive"))
      (node (ref "Q22") (pin "1") (pinfunction "E_1") (pintype "passive"))
      (node (ref "R12") (pin "2") (pinfunction "2_2") (pintype "passive"))
    )
    (net (code "8") (name "/CD1") (class "Default")
      (node (ref "Q25") (pin "1") (pinfunction "E_1") (pintype "passive"))
      (node (ref "Q26") (pin "1") (pinfunction "E_1") (pintype "passive"))
      (node (ref "R14") (pin "2") (pinfunction "2_2") (pintype "passive"))
    )
    (net (code "9") (name "/CD2") (class "Default")
      (node (ref "Q29") (pin "1") (pinfunction "E_1") (pintype "passive"))
      (node (ref "Q30") (pin "1") (pinfunction "E_1") (pintype "passive"))
      (node (ref "R16") (pin "2") (pinfunction "2_2") (pintype "passive"))
    )
    (net (code "10") (name "/CE1") (class "Default")
      (node (ref "Q33") (pin "1") (pinfunction "E_1") (pintype "passive"))
      (node (ref "Q34") (pin "1") (pinfunction "E_1") (pintype "passive"))
      (node (ref "R18") (pin "2") (pinfunction "2_2") (pintype "passive"))
    )
    (net (code "11") (name "/CE2") (class "Default")
      (node (ref "Q37") (pin "1") (pinfunction "E_1") (pintype "passive"))
      (node (ref "Q38") (pin "1") (pinfunction "E_1") (pintype "passive"))
      (node (ref "R20") (pin "2") (pinfunction "2_2") (pintype "passive"))
    )
    (net (code "12") (name "/CF1") (class "Default")
      (node (ref "Q41") (pin "1") (pinfunction "E_1") (pintype "passive"))
      (node (ref "Q42") (pin "1") (pinfunction "E_1") (pintype "passive"))
      (node (ref "R22") (pin "2") (pinfunction "2_2") (pintype "passive"))
    )
    (net (code "13") (name "/CF2") (class "Default")
      (node (ref "Q45") (pin "1") (pinfunction "E_1") (pintype "passive"))
      (node (ref "Q46") (pin "1") (pinfunction "E_1") (pintype "passive"))
      (node (ref "R24") (pin "2") (pinfunction "2_2") (pintype "passive"))
    )
    (net (code "14") (name "/CH1") (class "Default")
      (node (ref "Q49") (pin "1") (pinfunction "E_1") (pintype "passive"))
      (node (ref "Q50") (pin "1") (pinfunction "E_1") (pintype "passive"))
      (node (ref "R26") (pin "2") (pinfunction "2_2") (pintype "passive"))
    )
    (net (code "15") (name "/CH2") (class "Default")
      (node (ref "Q53") (pin "1") (pinfunction "E_1") (pintype "passive"))
      (node (ref "Q54") (pin "1") (pinfunction "E_1") (pintype "passive"))
      (node (ref "R28") (pin "2") (pinfunction "2_2") (pintype "passive"))
    )
    (net (code "16") (name "/CJ1") (class "Default")
      (node (ref "Q57") (pin "1") (pinfunction "E_1") (pintype "passive"))
      (node (ref "Q58") (pin "1") (pinfunction "E_1") (pintype "passive"))
      (node (ref "R30") (pin "2") (pinfunction "2_2") (pintype "passive"))
    )
    (net (code "17") (name "/CJ2") (class "Default")
      (node (ref "Q61") (pin "1") (pinfunction "E_1") (pintype "passive"))
      (node (ref "Q62") (pin "1") (pinfunction "E_1") (pintype "passive"))
      (node (ref "R32") (pin "2") (pinfunction "2_2") (pintype "passive"))
    )
    (net (code "18") (name "/CK1") (class "Default")
      (node (ref "Q65") (pin "1") (pinfunction "E_1") (pintype "passive"))
      (node (ref "Q66") (pin "1") (pinfunction "E_1") (pintype "passive"))
      (node (ref "R34") (pin "2") (pinfunction "2_2") (pintype "passive"))
    )
    (net (code "19") (name "/CK2") (class "Default")
      (node (ref "Q69") (pin "1") (pinfunction "E_1") (pintype "passive"))
      (node (ref "Q70") (pin "1") (pinfunction "E_1") (pintype "passive"))
      (node (ref "R36") (pin "2") (pinfunction "2_2") (pintype "passive"))
    )
    (net (code "20") (name "/CL1") (class "Default")
      (node (ref "Q3") (pin "1") (pinfunction "E_1") (pintype "passive"))
      (node (ref "Q4") (pin "1") (pinfunction "E_1") (pintype "passive"))
      (node (ref "R3") (pin "2") (pinfunction "2_2") (pintype "passive"))
    )
    (net (code "21") (name "/CL2") (class "Default")
      (node (ref "Q7") (pin "1") (pinfunction "E_1") (pintype "passive"))
      (node (ref "Q8") (pin "1") (pinfunction "E_1") (pintype "passive"))
      (node (ref "R5") (pin "2") (pinfunction "2_2") (pintype "passive"))
    )
    (net (code "22") (name "/CM1") (class "Default")
      (node (ref "Q11") (pin "1") (pinfunction "E_1") (pintype "passive"))
      (node (ref "Q12") (pin "1") (pinfunction "E_1") (pintype "passive"))
      (node (ref "R7") (pin "2") (pinfunction "2_2") (pintype "passive"))
    )
    (net (code "23") (name "/CM2") (class "Default")
      (node (ref "Q15") (pin "1") (pinfunction "E_1") (pintype "passive"))
      (node (ref "Q16") (pin "1") (pinfunction "E_1") (pintype "passive"))
      (node (ref "R9") (pin "2") (pinfunction "2_2") (pintype "passive"))
    )
    (net (code "24") (name "/CN1") (class "Default")
      (node (ref "Q19") (pin "1") (pinfunction "E_1") (pintype "passive"))
      (node (ref "Q20") (pin "1") (pinfunction "E_1") (pintype "passive"))
      (node (ref "R11") (pin "2") (pinfunction "2_2") (pintype "passive"))
    )
    (net (code "25") (name "/CN2") (class "Default")
      (node (ref "Q23") (pin "1") (pinfunction "E_1") (pintype "passive"))
      (node (ref "Q24") (pin "1") (pinfunction "E_1") (pintype "passive"))
      (node (ref "R13") (pin "2") (pinfunction "2_2") (pintype "passive"))
    )
    (net (code "26") (name "/CP1") (class "Default")
      (node (ref "Q27") (pin "1") (pinfunction "E_1") (pintype "passive"))
      (node (ref "Q28") (pin "1") (pinfunction "E_1") (pintype "passive"))
      (node (ref "R15") (pin "2") (pinfunction "2_2") (pintype "passive"))
    )
    (net (code "27") (name "/CP2") (class "Default")
      (node (ref "Q31") (pin "1") (pinfunction "E_1") (pintype "passive"))
      (node (ref "Q32") (pin "1") (pinfunction "E_1") (pintype "passive"))
      (node (ref "R17") (pin "2") (pinfunction "2_2") (pintype "passive"))
    )
    (net (code "28") (name "/CR1") (class "Default")
      (node (ref "Q35") (pin "1") (pinfunction "E_1") (pintype "passive"))
      (node (ref "Q36") (pin "1") (pinfunction "E_1") (pintype "passive"))
      (node (ref "R19") (pin "2") (pinfunction "2_2") (pintype "passive"))
    )
    (net (code "29") (name "/CR2") (class "Default")
      (node (ref "Q39") (pin "1") (pinfunction "E_1") (pintype "passive"))
      (node (ref "Q40") (pin "1") (pinfunction "E_1") (pintype "passive"))
      (node (ref "R21") (pin "2") (pinfunction "2_2") (pintype "passive"))
    )
    (net (code "30") (name "/CS1") (class "Default")
      (node (ref "Q43") (pin "1") (pinfunction "E_1") (pintype "passive"))
      (node (ref "Q44") (pin "1") (pinfunction "E_1") (pintype "passive"))
      (node (ref "R23") (pin "2") (pinfunction "2_2") (pintype "passive"))
    )
    (net (code "31") (name "/CS2") (class "Default")
      (node (ref "Q47") (pin "1") (pinfunction "E_1") (pintype "passive"))
      (node (ref "Q48") (pin "1") (pinfunction "E_1") (pintype "passive"))
      (node (ref "R25") (pin "2") (pinfunction "2_2") (pintype "passive"))
    )
    (net (code "32") (name "/CT1") (class "Default")
      (node (ref "Q51") (pin "1") (pinfunction "E_1") (pintype "passive"))
      (node (ref "Q52") (pin "1") (pinfunction "E_1") (pintype "passive"))
      (node (ref "R27") (pin "2") (pinfunction "2_2") (pintype "passive"))
    )
    (net (code "33") (name "/CT2") (class "Default")
      (node (ref "Q55") (pin "1") (pinfunction "E_1") (pintype "passive"))
      (node (ref "Q56") (pin "1") (pinfunction "E_1") (pintype "passive"))
      (node (ref "R29") (pin "2") (pinfunction "2_2") (pintype "passive"))
    )
    (net (code "34") (name "/CU1") (class "Default")
      (node (ref "Q59") (pin "1") (pinfunction "E_1") (pintype "passive"))
      (node (ref "Q60") (pin "1") (pinfunction "E_1") (pintype "passive"))
      (node (ref "R31") (pin "2") (pinfunction "2_2") (pintype "passive"))
    )
    (net (code "35") (name "/CU2") (class "Default")
      (node (ref "Q63") (pin "1") (pinfunction "E_1") (pintype "passive"))
      (node (ref "Q64") (pin "1") (pinfunction "E_1") (pintype "passive"))
      (node (ref "R33") (pin "2") (pinfunction "2_2") (pintype "passive"))
    )
    (net (code "36") (name "/CV1") (class "Default")
      (node (ref "Q67") (pin "1") (pinfunction "E_1") (pintype "passive"))
      (node (ref "Q68") (pin "1") (pinfunction "E_1") (pintype "passive"))
      (node (ref "R35") (pin "2") (pinfunction "2_2") (pintype "passive"))
    )
    (net (code "37") (name "/CV2") (class "Default")
      (node (ref "Q71") (pin "1") (pinfunction "E_1") (pintype "passive"))
      (node (ref "Q72") (pin "1") (pinfunction "E_1") (pintype "passive"))
      (node (ref "R37") (pin "2") (pinfunction "2_2") (pintype "passive"))
    )
    (net (code "38") (name "/RAA1") (class "Default")
      (node (ref "JP1") (pin "2") (pinfunction "2_2") (pintype "passive"))
      (node (ref "R2") (pin "1") (pinfunction "1_1") (pintype "passive"))
      (node (ref "REF") (pin "AA1") (pinfunction "P$2_AA1") (pintype "bidirectional"))
    )
    (net (code "39") (name "/RAA2") (class "Default")
      (node (ref "JP10") (pin "2") (pinfunction "2_2") (pintype "passive"))
      (node (ref "REF") (pin "AA2") (pinfunction "P$2_AA2") (pintype "bidirectional"))
    )
    (net (code "40") (name "/RAB1") (class "Default")
      (node (ref "JP2") (pin "2") (pinfunction "2_2") (pintype "passive"))
      (node (ref "R56") (pin "1") (pinfunction "1_1") (pintype "passive"))
      (node (ref "REF") (pin "AB1") (pinfunction "P$2_AB1") (pintype "bidirectional"))
    )
    (net (code "41") (name "/RAB2") (class "Default")
      (node (ref "JP11") (pin "2") (pinfunction "2_2") (pintype "passive"))
      (node (ref "REF") (pin "AB2") (pinfunction "P$2_AB2") (pintype "bidirectional"))
    )
    (net (code "42") (name "/RAC1") (class "Default")
      (node (ref "JP3") (pin "2") (pinfunction "2_2") (pintype "passive"))
      (node (ref "REF") (pin "AC1") (pinfunction "P$2_AC1") (pintype "bidirectional"))
    )
    (net (code "43") (name "/RAC2") (class "Default")
      (node (ref "JP12") (pin "2") (pinfunction "2_2") (pintype "passive"))
      (node (ref "REF") (pin "AC2") (pinfunction "P$2_AC2") (pintype "bidirectional"))
    )
    (net (code "44") (name "/RAD1") (class "Default")
      (node (ref "JP4") (pin "2") (pinfunction "2_2") (pintype "passive"))
      (node (ref "REF") (pin "AD1") (pinfunction "P$2_AD1") (pintype "bidirectional"))
    )
    (net (code "45") (name "/RAD2") (class "Default")
      (node (ref "JP13") (pin "2") (pinfunction "2_2") (pintype "passive"))
      (node (ref "REF") (pin "AD2") (pinfunction "P$2_AD2") (pintype "bidirectional"))
    )
    (net (code "46") (name "/RAE1") (class "Default")
      (node (ref "JP5") (pin "2") (pinfunction "2_2") (pintype "passive"))
      (node (ref "REF") (pin "AE1") (pinfunction "P$2_AE1") (pintype "bidirectional"))
    )
    (net (code "47") (name "/RAE2") (class "Default")
      (node (ref "JP14") (pin "2") (pinfunction "2_2") (pintype "passive"))
      (node (ref "REF") (pin "AE2") (pinfunction "P$2_AE2") (pintype "bidirectional"))
    )
    (net (code "48") (name "/RAF1") (class "Default")
      (node (ref "JP6") (pin "2") (pinfunction "2_2") (pintype "passive"))
      (node (ref "REF") (pin "AF1") (pinfunction "P$2_AF1") (pintype "bidirectional"))
    )
    (net (code "49") (name "/RAF2") (class "Default")
      (node (ref "JP15") (pin "2") (pinfunction "2_2") (pintype "passive"))
      (node (ref "REF") (pin "AF2") (pinfunction "P$2_AF2") (pintype "bidirectional"))
    )
    (net (code "50") (name "/RAH1") (class "Default")
      (node (ref "JP7") (pin "2") (pinfunction "2_2") (pintype "passive"))
      (node (ref "REF") (pin "AH1") (pinfunction "P$2_AH1") (pintype "bidirectional"))
    )
    (net (code "51") (name "/RAH2") (class "Default")
      (node (ref "JP16") (pin "2") (pinfunction "2_2") (pintype "passive"))
      (node (ref "REF") (pin "AH2") (pinfunction "P$2_AH2") (pintype "bidirectional"))
    )
    (net (code "52") (name "/RAJ1") (class "Default")
      (node (ref "JP8") (pin "2") (pinfunction "2_2") (pintype "passive"))
      (node (ref "REF") (pin "AJ1") (pinfunction "P$2_AJ1") (pintype "bidirectional"))
    )
    (net (code "53") (name "/RAJ2") (class "Default")
      (node (ref "JP17") (pin "2") (pinfunction "2_2") (pintype "passive"))
      (node (ref "REF") (pin "AJ2") (pinfunction "P$2_AJ2") (pintype "bidirectional"))
    )
    (net (code "54") (name "/RAK1") (class "Default")
      (node (ref "JP9") (pin "2") (pinfunction "2_2") (pintype "passive"))
      (node (ref "REF") (pin "AK1") (pinfunction "P$2_AK1") (pintype "bidirectional"))
    )
    (net (code "55") (name "/RAK2") (class "Default")
      (node (ref "JP18") (pin "2") (pinfunction "2_2") (pintype "passive"))
      (node (ref "REF") (pin "AK2") (pinfunction "P$2_AK2") (pintype "bidirectional"))
    )
    (net (code "56") (name "/RAL1") (class "Default")
      (node (ref "JP19") (pin "2") (pinfunction "2_2") (pintype "passive"))
      (node (ref "REF") (pin "AL1") (pinfunction "P$2_AL1") (pintype "bidirectional"))
    )
    (net (code "57") (name "/RAL2") (class "Default")
      (node (ref "JP28") (pin "2") (pinfunction "2_2") (pintype "passive"))
      (node (ref "REF") (pin "AL2") (pinfunction "P$2_AL2") (pintype "bidirectional"))
    )
    (net (code "58") (name "/RAM1") (class "Default")
      (node (ref "JP20") (pin "2") (pinfunction "2_2") (pintype "passive"))
      (node (ref "REF") (pin "AM1") (pinfunction "P$2_AM1") (pintype "bidirectional"))
    )
    (net (code "59") (name "/RAM2") (class "Default")
      (node (ref "JP29") (pin "2") (pinfunction "2_2") (pintype "passive"))
      (node (ref "REF") (pin "AM2") (pinfunction "P$2_AM2") (pintype "bidirectional"))
    )
    (net (code "60") (name "/RAN1") (class "Default")
      (node (ref "JP21") (pin "2") (pinfunction "2_2") (pintype "passive"))
      (node (ref "REF") (pin "AN1") (pinfunction "P$2_AN1") (pintype "bidirectional"))
    )
    (net (code "61") (name "/RAN2") (class "Default")
      (node (ref "JP30") (pin "2") (pinfunction "2_2") (pintype "passive"))
      (node (ref "REF") (pin "AN2") (pinfunction "P$2_AN2") (pintype "bidirectional"))
    )
    (net (code "62") (name "/RAP1") (class "Default")
      (node (ref "JP22") (pin "2") (pinfunction "2_2") (pintype "passive"))
      (node (ref "REF") (pin "AP1") (pinfunction "P$2_AP1") (pintype "bidirectional"))
    )
    (net (code "63") (name "/RAP2") (class "Default")
      (node (ref "JP31") (pin "2") (pinfunction "2_2") (pintype "passive"))
      (node (ref "REF") (pin "AP2") (pinfunction "P$2_AP2") (pintype "bidirectional"))
    )
    (net (code "64") (name "/RAR1") (class "Default")
      (node (ref "JP23") (pin "2") (pinfunction "2_2") (pintype "passive"))
      (node (ref "REF") (pin "AR1") (pinfunction "P$2_AR1") (pintype "bidirectional"))
    )
    (net (code "65") (name "/RAR2") (class "Default")
      (node (ref "JP32") (pin "2") (pinfunction "2_2") (pintype "passive"))
      (node (ref "REF") (pin "AR2") (pinfunction "P$2_AR2") (pintype "bidirectional"))
    )
    (net (code "66") (name "/RAS1") (class "Default")
      (node (ref "JP24") (pin "2") (pinfunction "2_2") (pintype "passive"))
      (node (ref "REF") (pin "AS1") (pinfunction "P$2_AS1") (pintype "bidirectional"))
    )
    (net (code "67") (name "/RAS2") (class "Default")
      (node (ref "JP33") (pin "2") (pinfunction "2_2") (pintype "passive"))
      (node (ref "REF") (pin "AS2") (pinfunction "P$2_AS2") (pintype "bidirectional"))
    )
    (net (code "68") (name "/RAT1") (class "Default")
      (node (ref "JP25") (pin "2") (pinfunction "2_2") (pintype "passive"))
      (node (ref "REF") (pin "AT1") (pinfunction "P$2_AT1") (pintype "bidirectional"))
    )
    (net (code "69") (name "/RAT2") (class "Default")
      (node (ref "JP34") (pin "2") (pinfunction "2_2") (pintype "passive"))
      (node (ref "REF") (pin "AT2") (pinfunction "P$2_AT2") (pintype "bidirectional"))
    )
    (net (code "70") (name "/RAU1") (class "Default")
      (node (ref "JP26") (pin "2") (pinfunction "2_2") (pintype "passive"))
      (node (ref "REF") (pin "AU1") (pinfunction "P$2_AU1") (pintype "bidirectional"))
    )
    (net (code "71") (name "/RAU2") (class "Default")
      (node (ref "JP35") (pin "2") (pinfunction "2_2") (pintype "passive"))
      (node (ref "REF") (pin "AU2") (pinfunction "P$2_AU2") (pintype "bidirectional"))
    )
    (net (code "72") (name "/RAV1") (class "Default")
      (node (ref "JP27") (pin "2") (pinfunction "2_2") (pintype "passive"))
      (node (ref "REF") (pin "AV1") (pinfunction "P$2_AV1") (pintype "bidirectional"))
    )
    (net (code "73") (name "/RAV2") (class "Default")
      (node (ref "JP36") (pin "2") (pinfunction "2_2") (pintype "passive"))
      (node (ref "REF") (pin "AV2") (pinfunction "P$2_AV2") (pintype "bidirectional"))
    )
    (net (code "74") (name "/RBA1") (class "Default")
      (node (ref "REF") (pin "BA1") (pinfunction "P$2_BA1") (pintype "bidirectional"))
    )
    (net (code "75") (name "/RBA2") (class "Default")
      (node (ref "REF") (pin "BA2") (pinfunction "P$2_BA2") (pintype "bidirectional"))
    )
    (net (code "76") (name "/RBB1") (class "Default")
      (node (ref "REF") (pin "BB1") (pinfunction "P$2_BB1") (pintype "bidirectional"))
    )
    (net (code "77") (name "/RBB2") (class "Default")
      (node (ref "REF") (pin "BB2") (pinfunction "P$2_BB2") (pintype "bidirectional"))
    )
    (net (code "78") (name "/RBC1") (class "Default")
      (node (ref "REF") (pin "BC1") (pinfunction "P$2_BC1") (pintype "bidirectional"))
    )
    (net (code "79") (name "/RBC2") (class "Default")
      (node (ref "REF") (pin "BC2") (pinfunction "P$2_BC2") (pintype "bidirectional"))
    )
    (net (code "80") (name "/RBD1") (class "Default")
      (node (ref "REF") (pin "BD1") (pinfunction "P$2_BD1") (pintype "bidirectional"))
    )
    (net (code "81") (name "/RBD2") (class "Default")
      (node (ref "REF") (pin "BD2") (pinfunction "P$2_BD2") (pintype "bidirectional"))
    )
    (net (code "82") (name "/RBE1") (class "Default")
      (node (ref "REF") (pin "BE1") (pinfunction "P$2_BE1") (pintype "bidirectional"))
    )
    (net (code "83") (name "/RBE2") (class "Default")
      (node (ref "REF") (pin "BE2") (pinfunction "P$2_BE2") (pintype "bidirectional"))
    )
    (net (code "84") (name "/RBF1") (class "Default")
      (node (ref "REF") (pin "BF1") (pinfunction "P$2_BF1") (pintype "bidirectional"))
    )
    (net (code "85") (name "/RBF2") (class "Default")
      (node (ref "REF") (pin "BF2") (pinfunction "P$2_BF2") (pintype "bidirectional"))
    )
    (net (code "86") (name "/RBH1") (class "Default")
      (node (ref "REF") (pin "BH1") (pinfunction "P$2_BH1") (pintype "bidirectional"))
    )
    (net (code "87") (name "/RBH2") (class "Default")
      (node (ref "REF") (pin "BH2") (pinfunction "P$2_BH2") (pintype "bidirectional"))
    )
    (net (code "88") (name "/RBJ1") (class "Default")
      (node (ref "REF") (pin "BJ1") (pinfunction "P$2_BJ1") (pintype "bidirectional"))
    )
    (net (code "89") (name "/RBJ2") (class "Default")
      (node (ref "REF") (pin "BJ2") (pinfunction "P$2_BJ2") (pintype "bidirectional"))
    )
    (net (code "90") (name "/RBK1") (class "Default")
      (node (ref "REF") (pin "BK1") (pinfunction "P$2_BK1") (pintype "bidirectional"))
    )
    (net (code "91") (name "/RBK2") (class "Default")
      (node (ref "REF") (pin "BK2") (pinfunction "P$2_BK2") (pintype "bidirectional"))
    )
    (net (code "92") (name "/RBL1") (class "Default")
      (node (ref "REF") (pin "BL1") (pinfunction "P$2_BL1") (pintype "bidirectional"))
    )
    (net (code "93") (name "/RBL2") (class "Default")
      (node (ref "REF") (pin "BL2") (pinfunction "P$2_BL2") (pintype "bidirectional"))
    )
    (net (code "94") (name "/RBM1") (class "Default")
      (node (ref "REF") (pin "BM1") (pinfunction "P$2_BM1") (pintype "bidirectional"))
    )
    (net (code "95") (name "/RBM2") (class "Default")
      (node (ref "REF") (pin "BM2") (pinfunction "P$2_BM2") (pintype "bidirectional"))
    )
    (net (code "96") (name "/RBN1") (class "Default")
      (node (ref "REF") (pin "BN1") (pinfunction "P$2_BN1") (pintype "bidirectional"))
    )
    (net (code "97") (name "/RBN2") (class "Default")
      (node (ref "REF") (pin "BN2") (pinfunction "P$2_BN2") (pintype "bidirectional"))
    )
    (net (code "98") (name "/RBP1") (class "Default")
      (node (ref "REF") (pin "BP1") (pinfunction "P$2_BP1") (pintype "bidirectional"))
    )
    (net (code "99") (name "/RBP2") (class "Default")
      (node (ref "REF") (pin "BP2") (pinfunction "P$2_BP2") (pintype "bidirectional"))
    )
    (net (code "100") (name "/RBR1") (class "Default")
      (node (ref "REF") (pin "BR1") (pinfunction "P$2_BR1") (pintype "bidirectional"))
    )
    (net (code "101") (name "/RBR2") (class "Default")
      (node (ref "REF") (pin "BR2") (pinfunction "P$2_BR2") (pintype "bidirectional"))
    )
    (net (code "102") (name "/RBS1") (class "Default")
      (node (ref "REF") (pin "BS1") (pinfunction "P$2_BS1") (pintype "bidirectional"))
    )
    (net (code "103") (name "/RBS2") (class "Default")
      (node (ref "REF") (pin "BS2") (pinfunction "P$2_BS2") (pintype "bidirectional"))
    )
    (net (code "104") (name "/RBT1") (class "Default")
      (node (ref "REF") (pin "BT1") (pinfunction "P$2_BT1") (pintype "bidirectional"))
    )
    (net (code "105") (name "/RBT2") (class "Default")
      (node (ref "REF") (pin "BT2") (pinfunction "P$2_BT2") (pintype "bidirectional"))
    )
    (net (code "106") (name "/RBU1") (class "Default")
      (node (ref "REF") (pin "BU1") (pinfunction "P$2_BU1") (pintype "bidirectional"))
    )
    (net (code "107") (name "/RBU2") (class "Default")
      (node (ref "REF") (pin "BU2") (pinfunction "P$2_BU2") (pintype "bidirectional"))
    )
    (net (code "108") (name "/RBV1") (class "Default")
      (node (ref "REF") (pin "BV1") (pinfunction "P$2_BV1") (pintype "bidirectional"))
    )
    (net (code "109") (name "/RBV2") (class "Default")
      (node (ref "REF") (pin "BV2") (pinfunction "P$2_BV2") (pintype "bidirectional"))
    )
    (net (code "110") (name "/T") (class "Default")
      (node (ref "JP10") (pin "3") (pinfunction "3_3") (pintype "passive"))
      (node (ref "JP11") (pin "3") (pinfunction "3_3") (pintype "passive"))
      (node (ref "JP12") (pin "3") (pinfunction "3_3") (pintype "passive"))
      (node (ref "JP13") (pin "3") (pinfunction "3_3") (pintype "passive"))
      (node (ref "JP14") (pin "3") (pinfunction "3_3") (pintype "passive"))
      (node (ref "JP15") (pin "3") (pinfunction "3_3") (pintype "passive"))
      (node (ref "JP16") (pin "3") (pinfunction "3_3") (pintype "passive"))
      (node (ref "JP17") (pin "3") (pinfunction "3_3") (pintype "passive"))
      (node (ref "JP18") (pin "3") (pinfunction "3_3") (pintype "passive"))
      (node (ref "JP19") (pin "3") (pinfunction "3_3") (pintype "passive"))
      (node (ref "JP20") (pin "3") (pinfunction "3_3") (pintype "passive"))
      (node (ref "JP21") (pin "3") (pinfunction "3_3") (pintype "passive"))
      (node (ref "JP22") (pin "3") (pinfunction "3_3") (pintype "passive"))
      (node (ref "JP23") (pin "3") (pinfunction "3_3") (pintype "passive"))
      (node (ref "JP24") (pin "3") (pinfunction "3_3") (pintype "passive"))
      (node (ref "JP25") (pin "3") (pinfunction "3_3") (pintype "passive"))
      (node (ref "JP26") (pin "3") (pinfunction "3_3") (pintype "passive"))
      (node (ref "JP27") (pin "3") (pinfunction "3_3") (pintype "passive"))
      (node (ref "JP28") (pin "3") (pinfunction "3_3") (pintype "passive"))
      (node (ref "JP29") (pin "3") (pinfunction "3_3") (pintype "passive"))
      (node (ref "JP3") (pin "3") (pinfunction "3_3") (pintype "passive"))
      (node (ref "JP30") (pin "3") (pinfunction "3_3") (pintype "passive"))
      (node (ref "JP31") (pin "3") (pinfunction "3_3") (pintype "passive"))
      (node (ref "JP32") (pin "3") (pinfunction "3_3") (pintype "passive"))
      (node (ref "JP33") (pin "3") (pinfunction "3_3") (pintype "passive"))
      (node (ref "JP34") (pin "3") (pinfunction "3_3") (pintype "passive"))
      (node (ref "JP35") (pin "3") (pinfunction "3_3") (pintype "passive"))
      (node (ref "JP36") (pin "3") (pinfunction "3_3") (pintype "passive"))
      (node (ref "JP4") (pin "3") (pinfunction "3_3") (pintype "passive"))
      (node (ref "JP5") (pin "3") (pinfunction "3_3") (pintype "passive"))
      (node (ref "JP6") (pin "3") (pinfunction "3_3") (pintype "passive"))
      (node (ref "JP7") (pin "3") (pinfunction "3_3") (pintype "passive"))
      (node (ref "JP8") (pin "3") (pinfunction "3_3") (pintype "passive"))
      (node (ref "JP9") (pin "3") (pinfunction "3_3") (pintype "passive"))
    )
    (net (code "111") (name "/TAA1") (class "Default")
      (node (ref "D1") (pin "AG") (pinfunction "AG_AG") (pintype "passive"))
      (node (ref "D1") (pin "AR") (pinfunction "AR_AR") (pintype "passive"))
      (node (ref "JP1") (pin "3") (pinfunction "3_3") (pintype "passive"))
      (node (ref "Q1") (pin "2") (pinfunction "B_2") (pintype "passive"))
      (node (ref "Q2") (pin "2") (pinfunction "B_2") (pintype "passive"))
      (node (ref "SV1") (pin "C") (pinfunction "3_C") (pintype "bidirectional"))
      (node (ref "TST") (pin "AA1") (pinfunction "P$2_AA1") (pintype "bidirectional"))
    )
    (net (code "112") (name "/TAA2") (class "Default")
      (node (ref "Q5") (pin "2") (pinfunction "B_2") (pintype "passive"))
      (node (ref "Q6") (pin "2") (pinfunction "B_2") (pintype "passive"))
      (node (ref "SV1") (pin "B") (pinfunction "2_B") (pintype "bidirectional"))
      (node (ref "TST") (pin "AA2") (pinfunction "P$2_AA2") (pintype "bidirectional"))
    )
    (net (code "113") (name "/TAB1") (class "Default")
      (node (ref "D2") (pin "AG") (pinfunction "AG_AG") (pintype "passive"))
      (node (ref "D2") (pin "AR") (pinfunction "AR_AR") (pintype "passive"))
      (node (ref "JP2") (pin "3") (pinfunction "3_3") (pintype "passive"))
      (node (ref "Q10") (pin "2") (pinfunction "B_2") (pintype "passive"))
      (node (ref "Q9") (pin "2") (pinfunction "B_2") (pintype "passive"))
      (node (ref "SV1") (pin "D") (pinfunction "4_D") (pintype "bidirectional"))
      (node (ref "TST") (pin "AB1") (pinfunction "P$2_AB1") (pintype "bidirectional"))
    )
    (net (code "114") (name "/TAB2") (class "Default")
      (node (ref "Q13") (pin "2") (pinfunction "B_2") (pintype "passive"))
      (node (ref "Q14") (pin "2") (pinfunction "B_2") (pintype "passive"))
      (node (ref "SV1") (pin "A") (pinfunction "1_A") (pintype "bidirectional"))
      (node (ref "TST") (pin "AB2") (pinfunction "P$2_AB2") (pintype "bidirectional"))
    )
    (net (code "115") (name "/TAC1") (class "Default")
      (node (ref "Q17") (pin "2") (pinfunction "B_2") (pintype "passive"))
      (node (ref "Q18") (pin "2") (pinfunction "B_2") (pintype "passive"))
      (node (ref "SV1") (pin "P") (pinfunction "13_P") (pintype "bidirectional"))
      (node (ref "SV1") (pin "S") (pinfunction "15_S") (pintype "bidirectional"))
      (node (ref "TST") (pin "AC1") (pinfunction "P$2_AC1") (pintype "bidirectional"))
    )
    (net (code "116") (name "/TAC2") (class "Default")
      (node (ref "Q21") (pin "2") (pinfunction "B_2") (pintype "passive"))
      (node (ref "Q22") (pin "2") (pinfunction "B_2") (pintype "passive"))
      (node (ref "SV1") (pin "E") (pinfunction "5_E") (pintype "bidirectional"))
      (node (ref "TST") (pin "AC2") (pinfunction "P$2_AC2") (pintype "bidirectional"))
    )
    (net (code "117") (name "/TAD1") (class "Default")
      (node (ref "Q25") (pin "2") (pinfunction "B_2") (pintype "passive"))
      (node (ref "Q26") (pin "2") (pinfunction "B_2") (pintype "passive"))
      (node (ref "SV1") (pin "J") (pinfunction "8_J") (pintype "bidirectional"))
      (node (ref "TST") (pin "AD1") (pinfunction "P$2_AD1") (pintype "bidirectional"))
    )
    (net (code "118") (name "/TAD2") (class "Default")
      (node (ref "Q29") (pin "2") (pinfunction "B_2") (pintype "passive"))
      (node (ref "Q30") (pin "2") (pinfunction "B_2") (pintype "passive"))
      (node (ref "SV1") (pin "F") (pinfunction "6_F") (pintype "bidirectional"))
      (node (ref "TST") (pin "AD2") (pinfunction "P$2_AD2") (pintype "bidirectional"))
    )
    (net (code "119") (name "/TAE1") (class "Default")
      (node (ref "Q33") (pin "2") (pinfunction "B_2") (pintype "passive"))
      (node (ref "Q34") (pin "2") (pinfunction "B_2") (pintype "passive"))
      (node (ref "SV1") (pin "N") (pinfunction "12_N") (pintype "bidirectional"))
      (node (ref "TST") (pin "AE1") (pinfunction "P$2_AE1") (pintype "bidirectional"))
    )
    (net (code "120") (name "/TAE2") (class "Default")
      (node (ref "Q37") (pin "2") (pinfunction "B_2") (pintype "passive"))
      (node (ref "Q38") (pin "2") (pinfunction "B_2") (pintype "passive"))
      (node (ref "SV1") (pin "L") (pinfunction "10_L") (pintype "bidirectional"))
      (node (ref "TST") (pin "AE2") (pinfunction "P$2_AE2") (pintype "bidirectional"))
    )
    (net (code "121") (name "/TAF1") (class "Default")
      (node (ref "Q41") (pin "2") (pinfunction "B_2") (pintype "passive"))
      (node (ref "Q42") (pin "2") (pinfunction "B_2") (pintype "passive"))
      (node (ref "SV1") (pin "U") (pinfunction "17_U") (pintype "bidirectional"))
      (node (ref "TST") (pin "AF1") (pinfunction "P$2_AF1") (pintype "bidirectional"))
    )
    (net (code "122") (name "/TAF2") (class "Default")
      (node (ref "Q45") (pin "2") (pinfunction "B_2") (pintype "passive"))
      (node (ref "Q46") (pin "2") (pinfunction "B_2") (pintype "passive"))
      (node (ref "SV1") (pin "H") (pinfunction "7_H") (pintype "bidirectional"))
      (node (ref "SV1") (pin "K") (pinfunction "9_K") (pintype "bidirectional"))
      (node (ref "TST") (pin "AF2") (pinfunction "P$2_AF2") (pintype "bidirectional"))
    )
    (net (code "123") (name "/TAH1") (class "Default")
      (node (ref "Q49") (pin "2") (pinfunction "B_2") (pintype "passive"))
      (node (ref "Q50") (pin "2") (pinfunction "B_2") (pintype "passive"))
      (node (ref "SV1") (pin "T") (pinfunction "16_T") (pintype "bidirectional"))
      (node (ref "TST") (pin "AH1") (pinfunction "P$2_AH1") (pintype "bidirectional"))
    )
    (net (code "124") (name "/TAH2") (class "Default")
      (node (ref "Q53") (pin "2") (pinfunction "B_2") (pintype "passive"))
      (node (ref "Q54") (pin "2") (pinfunction "B_2") (pintype "passive"))
      (node (ref "SV1") (pin "R") (pinfunction "14_R") (pintype "bidirectional"))
      (node (ref "TST") (pin "AH2") (pinfunction "P$2_AH2") (pintype "bidirectional"))
    )
    (net (code "125") (name "/TAJ1") (class "Default")
      (node (ref "Q57") (pin "2") (pinfunction "B_2") (pintype "passive"))
      (node (ref "Q58") (pin "2") (pinfunction "B_2") (pintype "passive"))
      (node (ref "SV1") (pin "X") (pinfunction "20_X") (pintype "bidirectional"))
      (node (ref "TST") (pin "AJ1") (pinfunction "P$2_AJ1") (pintype "bidirectional"))
    )
    (net (code "126") (name "/TAJ2") (class "Default")
      (node (ref "Q61") (pin "2") (pinfunction "B_2") (pintype "passive"))
      (node (ref "Q62") (pin "2") (pinfunction "B_2") (pintype "passive"))
      (node (ref "SV1") (pin "M") (pinfunction "11_M") (pintype "bidirectional"))
      (node (ref "TST") (pin "AJ2") (pinfunction "P$2_AJ2") (pintype "bidirectional"))
    )
    (net (code "127") (name "/TAK1") (class "Default")
      (node (ref "Q65") (pin "2") (pinfunction "B_2") (pintype "passive"))
      (node (ref "Q66") (pin "2") (pinfunction "B_2") (pintype "passive"))
      (node (ref "SV1") (pin "AA") (pinfunction "23_AA") (pintype "bidirectional"))
      (node (ref "SV1") (pin "Y") (pinfunction "21_Y") (pintype "bidirectional"))
      (node (ref "TST") (pin "AK1") (pinfunction "P$2_AK1") (pintype "bidirectional"))
    )
    (net (code "128") (name "/TAK2") (class "Default")
      (node (ref "Q69") (pin "2") (pinfunction "B_2") (pintype "passive"))
      (node (ref "Q70") (pin "2") (pinfunction "B_2") (pintype "passive"))
      (node (ref "SV1") (pin "V") (pinfunction "18_V") (pintype "bidirectional"))
      (node (ref "TST") (pin "AK2") (pinfunction "P$2_AK2") (pintype "bidirectional"))
    )
    (net (code "129") (name "/TAL1") (class "Default")
      (node (ref "Q3") (pin "2") (pinfunction "B_2") (pintype "passive"))
      (node (ref "Q4") (pin "2") (pinfunction "B_2") (pintype "passive"))
      (node (ref "SV1") (pin "BB") (pinfunction "24_BB") (pintype "bidirectional"))
      (node (ref "TST") (pin "AL1") (pinfunction "P$2_AL1") (pintype "bidirectional"))
    )
    (net (code "130") (name "/TAL2") (class "Default")
      (node (ref "Q7") (pin "2") (pinfunction "B_2") (pintype "passive"))
      (node (ref "Q8") (pin "2") (pinfunction "B_2") (pintype "passive"))
      (node (ref "SV1") (pin "W") (pinfunction "19_W") (pintype "bidirectional"))
      (node (ref "TST") (pin "AL2") (pinfunction "P$2_AL2") (pintype "bidirectional"))
    )
    (net (code "131") (name "/TAM1") (class "Default")
      (node (ref "Q11") (pin "2") (pinfunction "B_2") (pintype "passive"))
      (node (ref "Q12") (pin "2") (pinfunction "B_2") (pintype "passive"))
      (node (ref "SV1") (pin "FF") (pinfunction "28_FF") (pintype "bidirectional"))
      (node (ref "TST") (pin "AM1") (pinfunction "P$2_AM1") (pintype "bidirectional"))
    )
    (net (code "132") (name "/TAM2") (class "Default")
      (node (ref "Q15") (pin "2") (pinfunction "B_2") (pintype "passive"))
      (node (ref "Q16") (pin "2") (pinfunction "B_2") (pintype "passive"))
      (node (ref "SV1") (pin "Z") (pinfunction "22_Z") (pintype "bidirectional"))
      (node (ref "TST") (pin "AM2") (pinfunction "P$2_AM2") (pintype "bidirectional"))
    )
    (net (code "133") (name "/TAN1") (class "Default")
      (node (ref "Q19") (pin "2") (pinfunction "B_2") (pintype "passive"))
      (node (ref "Q20") (pin "2") (pinfunction "B_2") (pintype "passive"))
      (node (ref "SV1") (pin "CC") (pinfunction "25_CC") (pintype "bidirectional"))
      (node (ref "TST") (pin "AN1") (pinfunction "P$2_AN1") (pintype "bidirectional"))
    )
    (net (code "134") (name "/TAN2") (class "Default")
      (node (ref "Q23") (pin "2") (pinfunction "B_2") (pintype "passive"))
      (node (ref "Q24") (pin "2") (pinfunction "B_2") (pintype "passive"))
      (node (ref "SV1") (pin "EE") (pinfunction "27_EE") (pintype "bidirectional"))
      (node (ref "TST") (pin "AN2") (pinfunction "P$2_AN2") (pintype "bidirectional"))
    )
    (net (code "135") (name "/TAP1") (class "Default")
      (node (ref "Q27") (pin "2") (pinfunction "B_2") (pintype "passive"))
      (node (ref "Q28") (pin "2") (pinfunction "B_2") (pintype "passive"))
      (node (ref "SV1") (pin "LL") (pinfunction "32_LL") (pintype "bidirectional"))
      (node (ref "TST") (pin "AP1") (pinfunction "P$2_AP1") (pintype "bidirectional"))
    )
    (net (code "136") (name "/TAP2") (class "Default")
      (node (ref "Q31") (pin "2") (pinfunction "B_2") (pintype "passive"))
      (node (ref "Q32") (pin "2") (pinfunction "B_2") (pintype "passive"))
      (node (ref "SV1") (pin "DD") (pinfunction "26_DD") (pintype "bidirectional"))
      (node (ref "TST") (pin "AP2") (pinfunction "P$2_AP2") (pintype "bidirectional"))
    )
    (net (code "137") (name "/TAR1") (class "Default")
      (node (ref "Q35") (pin "2") (pinfunction "B_2") (pintype "passive"))
      (node (ref "Q36") (pin "2") (pinfunction "B_2") (pintype "passive"))
      (node (ref "SV1") (pin "HH") (pinfunction "29_HH") (pintype "bidirectional"))
      (node (ref "SV1") (pin "KK") (pinfunction "31_KK") (pintype "bidirectional"))
      (node (ref "SV1") (pin "MM") (pinfunction "33_MM") (pintype "bidirectional"))
      (node (ref "TST") (pin "AR1") (pinfunction "P$2_AR1") (pintype "bidirectional"))
    )
    (net (code "138") (name "/TAR2") (class "Default")
      (node (ref "Q39") (pin "2") (pinfunction "B_2") (pintype "passive"))
      (node (ref "Q40") (pin "2") (pinfunction "B_2") (pintype "passive"))
      (node (ref "SV1") (pin "PP") (pinfunction "35_PP") (pintype "bidirectional"))
      (node (ref "TST") (pin "AR2") (pinfunction "P$2_AR2") (pintype "bidirectional"))
    )
    (net (code "139") (name "/TAS1") (class "Default")
      (node (ref "Q43") (pin "2") (pinfunction "B_2") (pintype "passive"))
      (node (ref "Q44") (pin "2") (pinfunction "B_2") (pintype "passive"))
      (node (ref "SV1") (pin "RR") (pinfunction "36_RR") (pintype "bidirectional"))
      (node (ref "TST") (pin "AS1") (pinfunction "P$2_AS1") (pintype "bidirectional"))
    )
    (net (code "140") (name "/TAS2") (class "Default")
      (node (ref "Q47") (pin "2") (pinfunction "B_2") (pintype "passive"))
      (node (ref "Q48") (pin "2") (pinfunction "B_2") (pintype "passive"))
      (node (ref "SV1") (pin "JJ") (pinfunction "30_JJ") (pintype "bidirectional"))
      (node (ref "TST") (pin "AS2") (pinfunction "P$2_AS2") (pintype "bidirectional"))
    )
    (net (code "141") (name "/TAT1") (class "Default")
      (node (ref "Q51") (pin "2") (pinfunction "B_2") (pintype "passive"))
      (node (ref "Q52") (pin "2") (pinfunction "B_2") (pintype "passive"))
      (node (ref "SV1") (pin "SS") (pinfunction "37_SS") (pintype "bidirectional"))
      (node (ref "TST") (pin "AT1") (pinfunction "P$2_AT1") (pintype "bidirectional"))
    )
    (net (code "142") (name "/TAT2") (class "Default")
      (node (ref "Q55") (pin "2") (pinfunction "B_2") (pintype "passive"))
      (node (ref "Q56") (pin "2") (pinfunction "B_2") (pintype "passive"))
      (node (ref "SV1") (pin "NN") (pinfunction "34_NN") (pintype "bidirectional"))
      (node (ref "TST") (pin "AT2") (pinfunction "P$2_AT2") (pintype "bidirectional"))
    )
    (net (code "143") (name "/TAU1") (class "Default")
      (node (ref "Q59") (pin "2") (pinfunction "B_2") (pintype "passive"))
      (node (ref "Q60") (pin "2") (pinfunction "B_2") (pintype "passive"))
      (node (ref "SV1") (pin "UU") (pinfunction "39_UU") (pintype "bidirectional"))
      (node (ref "TST") (pin "AU1") (pinfunction "P$2_AU1") (pintype "bidirectional"))
    )
    (net (code "144") (name "/TAU2") (class "Default")
      (node (ref "Q63") (pin "2") (pinfunction "B_2") (pintype "passive"))
      (node (ref "Q64") (pin "2") (pinfunction "B_2") (pintype "passive"))
      (node (ref "TST") (pin "AU2") (pinfunction "P$2_AU2") (pintype "bidirectional"))
    )
    (net (code "145") (name "/TAV1") (class "Default")
      (node (ref "Q67") (pin "2") (pinfunction "B_2") (pintype "passive"))
      (node (ref "Q68") (pin "2") (pinfunction "B_2") (pintype "passive"))
      (node (ref "SV1") (pin "VV") (pinfunction "40_VV") (pintype "bidirectional"))
      (node (ref "TST") (pin "AV1") (pinfunction "P$2_AV1") (pintype "bidirectional"))
    )
    (net (code "146") (name "/TAV2") (class "Default")
      (node (ref "Q71") (pin "2") (pinfunction "B_2") (pintype "passive"))
      (node (ref "Q72") (pin "2") (pinfunction "B_2") (pintype "passive"))
      (node (ref "SV1") (pin "TT") (pinfunction "38_TT") (pintype "bidirectional"))
      (node (ref "TST") (pin "AV2") (pinfunction "P$2_AV2") (pintype "bidirectional"))
    )
    (net (code "147") (name "/TBA1") (class "Default")
      (node (ref "SV2") (pin "C") (pinfunction "3_C") (pintype "bidirectional"))
      (node (ref "TST") (pin "BA1") (pinfunction "P$2_BA1") (pintype "bidirectional"))
    )
    (net (code "148") (name "/TBA2") (class "Default")
      (node (ref "SV2") (pin "B") (pinfunction "2_B") (pintype "bidirectional"))
      (node (ref "TST") (pin "BA2") (pinfunction "P$2_BA2") (pintype "bidirectional"))
    )
    (net (code "149") (name "/TBB1") (class "Default")
      (node (ref "SV2") (pin "D") (pinfunction "4_D") (pintype "bidirectional"))
      (node (ref "TST") (pin "BB1") (pinfunction "P$2_BB1") (pintype "bidirectional"))
    )
    (net (code "150") (name "/TBB2") (class "Default")
      (node (ref "SV2") (pin "A") (pinfunction "1_A") (pintype "bidirectional"))
      (node (ref "TST") (pin "BB2") (pinfunction "P$2_BB2") (pintype "bidirectional"))
    )
    (net (code "151") (name "/TBC1") (class "Default")
      (node (ref "SV2") (pin "P") (pinfunction "13_P") (pintype "bidirectional"))
      (node (ref "SV2") (pin "S") (pinfunction "15_S") (pintype "bidirectional"))
      (node (ref "TST") (pin "BC1") (pinfunction "P$2_BC1") (pintype "bidirectional"))
    )
    (net (code "152") (name "/TBC2") (class "Default")
      (node (ref "SV2") (pin "E") (pinfunction "5_E") (pintype "bidirectional"))
      (node (ref "TST") (pin "BC2") (pinfunction "P$2_BC2") (pintype "bidirectional"))
    )
    (net (code "153") (name "/TBD1") (class "Default")
      (node (ref "SV2") (pin "J") (pinfunction "8_J") (pintype "bidirectional"))
      (node (ref "TST") (pin "BD1") (pinfunction "P$2_BD1") (pintype "bidirectional"))
    )
    (net (code "154") (name "/TBD2") (class "Default")
      (node (ref "SV2") (pin "F") (pinfunction "6_F") (pintype "bidirectional"))
      (node (ref "TST") (pin "BD2") (pinfunction "P$2_BD2") (pintype "bidirectional"))
    )
    (net (code "155") (name "/TBE1") (class "Default")
      (node (ref "SV2") (pin "N") (pinfunction "12_N") (pintype "bidirectional"))
      (node (ref "TST") (pin "BE1") (pinfunction "P$2_BE1") (pintype "bidirectional"))
    )
    (net (code "156") (name "/TBE2") (class "Default")
      (node (ref "SV2") (pin "L") (pinfunction "10_L") (pintype "bidirectional"))
      (node (ref "TST") (pin "BE2") (pinfunction "P$2_BE2") (pintype "bidirectional"))
    )
    (net (code "157") (name "/TBF1") (class "Default")
      (node (ref "SV2") (pin "U") (pinfunction "17_U") (pintype "bidirectional"))
      (node (ref "TST") (pin "BF1") (pinfunction "P$2_BF1") (pintype "bidirectional"))
    )
    (net (code "158") (name "/TBF2") (class "Default")
      (node (ref "SV2") (pin "H") (pinfunction "7_H") (pintype "bidirectional"))
      (node (ref "SV2") (pin "K") (pinfunction "9_K") (pintype "bidirectional"))
      (node (ref "TST") (pin "BF2") (pinfunction "P$2_BF2") (pintype "bidirectional"))
    )
    (net (code "159") (name "/TBH1") (class "Default")
      (node (ref "SV2") (pin "T") (pinfunction "16_T") (pintype "bidirectional"))
      (node (ref "TST") (pin "BH1") (pinfunction "P$2_BH1") (pintype "bidirectional"))
    )
    (net (code "160") (name "/TBH2") (class "Default")
      (node (ref "SV2") (pin "R") (pinfunction "14_R") (pintype "bidirectional"))
      (node (ref "TST") (pin "BH2") (pinfunction "P$2_BH2") (pintype "bidirectional"))
    )
    (net (code "161") (name "/TBJ1") (class "Default")
      (node (ref "SV2") (pin "X") (pinfunction "20_X") (pintype "bidirectional"))
      (node (ref "TST") (pin "BJ1") (pinfunction "P$2_BJ1") (pintype "bidirectional"))
    )
    (net (code "162") (name "/TBJ2") (class "Default")
      (node (ref "SV2") (pin "M") (pinfunction "11_M") (pintype "bidirectional"))
      (node (ref "TST") (pin "BJ2") (pinfunction "P$2_BJ2") (pintype "bidirectional"))
    )
    (net (code "163") (name "/TBK1") (class "Default")
      (node (ref "SV2") (pin "AA") (pinfunction "23_AA") (pintype "bidirectional"))
      (node (ref "SV2") (pin "Y") (pinfunction "21_Y") (pintype "bidirectional"))
      (node (ref "TST") (pin "BK1") (pinfunction "P$2_BK1") (pintype "bidirectional"))
    )
    (net (code "164") (name "/TBK2") (class "Default")
      (node (ref "SV2") (pin "V") (pinfunction "18_V") (pintype "bidirectional"))
      (node (ref "TST") (pin "BK2") (pinfunction "P$2_BK2") (pintype "bidirectional"))
    )
    (net (code "165") (name "/TBL1") (class "Default")
      (node (ref "SV2") (pin "BB") (pinfunction "24_BB") (pintype "bidirectional"))
      (node (ref "TST") (pin "BL1") (pinfunction "P$2_BL1") (pintype "bidirectional"))
    )
    (net (code "166") (name "/TBL2") (class "Default")
      (node (ref "SV2") (pin "W") (pinfunction "19_W") (pintype "bidirectional"))
      (node (ref "TST") (pin "BL2") (pinfunction "P$2_BL2") (pintype "bidirectional"))
    )
    (net (code "167") (name "/TBM1") (class "Default")
      (node (ref "SV2") (pin "FF") (pinfunction "28_FF") (pintype "bidirectional"))
      (node (ref "TST") (pin "BM1") (pinfunction "P$2_BM1") (pintype "bidirectional"))
    )
    (net (code "168") (name "/TBM2") (class "Default")
      (node (ref "SV2") (pin "Z") (pinfunction "22_Z") (pintype "bidirectional"))
      (node (ref "TST") (pin "BM2") (pinfunction "P$2_BM2") (pintype "bidirectional"))
    )
    (net (code "169") (name "/TBN1") (class "Default")
      (node (ref "SV2") (pin "CC") (pinfunction "25_CC") (pintype "bidirectional"))
      (node (ref "TST") (pin "BN1") (pinfunction "P$2_BN1") (pintype "bidirectional"))
    )
    (net (code "170") (name "/TBN2") (class "Default")
      (node (ref "SV2") (pin "EE") (pinfunction "27_EE") (pintype "bidirectional"))
      (node (ref "TST") (pin "BN2") (pinfunction "P$2_BN2") (pintype "bidirectional"))
    )
    (net (code "171") (name "/TBP1") (class "Default")
      (node (ref "SV2") (pin "LL") (pinfunction "32_LL") (pintype "bidirectional"))
      (node (ref "TST") (pin "BP1") (pinfunction "P$2_BP1") (pintype "bidirectional"))
    )
    (net (code "172") (name "/TBP2") (class "Default")
      (node (ref "SV2") (pin "DD") (pinfunction "26_DD") (pintype "bidirectional"))
      (node (ref "TST") (pin "BP2") (pinfunction "P$2_BP2") (pintype "bidirectional"))
    )
    (net (code "173") (name "/TBR1") (class "Default")
      (node (ref "SV2") (pin "HH") (pinfunction "29_HH") (pintype "bidirectional"))
      (node (ref "SV2") (pin "KK") (pinfunction "31_KK") (pintype "bidirectional"))
      (node (ref "SV2") (pin "MM") (pinfunction "33_MM") (pintype "bidirectional"))
      (node (ref "TST") (pin "BR1") (pinfunction "P$2_BR1") (pintype "bidirectional"))
    )
    (net (code "174") (name "/TBR2") (class "Default")
      (node (ref "SV2") (pin "PP") (pinfunction "35_PP") (pintype "bidirectional"))
      (node (ref "TST") (pin "BR2") (pinfunction "P$2_BR2") (pintype "bidirectional"))
    )
    (net (code "175") (name "/TBS1") (class "Default")
      (node (ref "SV2") (pin "RR") (pinfunction "36_RR") (pintype "bidirectional"))
      (node (ref "TST") (pin "BS1") (pinfunction "P$2_BS1") (pintype "bidirectional"))
    )
    (net (code "176") (name "/TBS2") (class "Default")
      (node (ref "SV2") (pin "JJ") (pinfunction "30_JJ") (pintype "bidirectional"))
      (node (ref "TST") (pin "BS2") (pinfunction "P$2_BS2") (pintype "bidirectional"))
    )
    (net (code "177") (name "/TBT1") (class "Default")
      (node (ref "SV2") (pin "SS") (pinfunction "37_SS") (pintype "bidirectional"))
      (node (ref "TST") (pin "BT1") (pinfunction "P$2_BT1") (pintype "bidirectional"))
    )
    (net (code "178") (name "/TBT2") (class "Default")
      (node (ref "SV2") (pin "NN") (pinfunction "34_NN") (pintype "bidirectional"))
      (node (ref "TST") (pin "BT2") (pinfunction "P$2_BT2") (pintype "bidirectional"))
    )
    (net (code "179") (name "/TBU1") (class "Default")
      (node (ref "SV2") (pin "UU") (pinfunction "39_UU") (pintype "bidirectional"))
      (node (ref "TST") (pin "BU1") (pinfunction "P$2_BU1") (pintype "bidirectional"))
    )
    (net (code "180") (name "/TBU2") (class "Default")
      (node (ref "TST") (pin "BU2") (pinfunction "P$2_BU2") (pintype "bidirectional"))
    )
    (net (code "181") (name "/TBV1") (class "Default")
      (node (ref "SV2") (pin "VV") (pinfunction "40_VV") (pintype "bidirectional"))
      (node (ref "TST") (pin "BV1") (pinfunction "P$2_BV1") (pintype "bidirectional"))
    )
    (net (code "182") (name "/TBV2") (class "Default")
      (node (ref "SV2") (pin "TT") (pinfunction "38_TT") (pintype "bidirectional"))
      (node (ref "TST") (pin "BV2") (pinfunction "P$2_BV2") (pintype "bidirectional"))
    )
    (net (code "183") (name "GND") (class "Default")
      (node (ref "R1") (pin "1") (pinfunction "1_1") (pintype "passive"))
      (node (ref "R10") (pin "1") (pinfunction "1_1") (pintype "passive"))
      (node (ref "R11") (pin "1") (pinfunction "1_1") (pintype "passive"))
      (node (ref "R12") (pin "1") (pinfunction "1_1") (pintype "passive"))
      (node (ref "R13") (pin "1") (pinfunction "1_1") (pintype "passive"))
      (node (ref "R14") (pin "1") (pinfunction "1_1") (pintype "passive"))
      (node (ref "R15") (pin "1") (pinfunction "1_1") (pintype "passive"))
      (node (ref "R16") (pin "1") (pinfunction "1_1") (pintype "passive"))
      (node (ref "R17") (pin "1") (pinfunction "1_1") (pintype "passive"))
      (node (ref "R18") (pin "1") (pinfunction "1_1") (pintype "passive"))
      (node (ref "R19") (pin "1") (pinfunction "1_1") (pintype "passive"))
      (node (ref "R20") (pin "1") (pinfunction "1_1") (pintype "passive"))
      (node (ref "R21") (pin "1") (pinfunction "1_1") (pintype "passive"))
      (node (ref "R22") (pin "1") (pinfunction "1_1") (pintype "passive"))
      (node (ref "R23") (pin "1") (pinfunction "1_1") (pintype "passive"))
      (node (ref "R24") (pin "1") (pinfunction "1_1") (pintype "passive"))
      (node (ref "R25") (pin "1") (pinfunction "1_1") (pintype "passive"))
      (node (ref "R26") (pin "1") (pinfunction "1_1") (pintype "passive"))
      (node (ref "R27") (pin "1") (pinfunction "1_1") (pintype "passive"))
      (node (ref "R28") (pin "1") (pinfunction "1_1") (pintype "passive"))
      (node (ref "R29") (pin "1") (pinfunction "1_1") (pintype "passive"))
      (node (ref "R3") (pin "1") (pinfunction "1_1") (pintype "passive"))
      (node (ref "R30") (pin "1") (pinfunction "1_1") (pintype "passive"))
      (node (ref "R31") (pin "1") (pinfunction "1_1") (pintype "passive"))
      (node (ref "R32") (pin "1") (pinfunction "1_1") (pintype "passive"))
      (node (ref "R33") (pin "1") (pinfunction "1_1") (pintype "passive"))
      (node (ref "R34") (pin "1") (pinfunction "1_1") (pintype "passive"))
      (node (ref "R35") (pin "1") (pinfunction "1_1") (pintype "passive"))
      (node (ref "R36") (pin "1") (pinfunction "1_1") (pintype "passive"))
      (node (ref "R37") (pin "1") (pinfunction "1_1") (pintype "passive"))
      (node (ref "R4") (pin "1") (pinfunction "1_1") (pintype "passive"))
      (node (ref "R5") (pin "1") (pinfunction "1_1") (pintype "passive"))
      (node (ref "R6") (pin "1") (pinfunction "1_1") (pintype "passive"))
      (node (ref "R7") (pin "1") (pinfunction "1_1") (pintype "passive"))
      (node (ref "R8") (pin "1") (pinfunction "1_1") (pintype "passive"))
      (node (ref "R9") (pin "1") (pinfunction "1_1") (pintype "passive"))
    )
    (net (code "184") (name "Net-(D1-C)") (class "Default")
      (node (ref "D1") (pin "K") (pinfunction "C_K") (pintype "passive"))
      (node (ref "R2") (pin "2") (pinfunction "2_2") (pintype "passive"))
    )
    (net (code "185") (name "Net-(D2-C)") (class "Default")
      (node (ref "D2") (pin "K") (pinfunction "C_K") (pintype "passive"))
      (node (ref "R56") (pin "2") (pinfunction "2_2") (pintype "passive"))
    )
    (net (code "186") (name "Net-(Q1-C)") (class "Default")
      (node (ref "Q1") (pin "3") (pinfunction "C_3") (pintype "passive"))
      (node (ref "R57") (pin "1") (pinfunction "1_1") (pintype "passive"))
    )
    (net (code "187") (name "Net-(Q2-C)") (class "Default")
      (node (ref "Q2") (pin "3") (pinfunction "C_3") (pintype "passive"))
      (node (ref "R39") (pin "2") (pinfunction "2_2") (pintype "passive"))
    )
    (net (code "188") (name "Net-(Q3-C)") (class "Default")
      (node (ref "Q3") (pin "3") (pinfunction "C_3") (pintype "passive"))
      (node (ref "R66") (pin "1") (pinfunction "1_1") (pintype "passive"))
    )
    (net (code "189") (name "Net-(Q4-C)") (class "Default")
      (node (ref "Q4") (pin "3") (pinfunction "C_3") (pintype "passive"))
      (node (ref "R93") (pin "2") (pinfunction "2_2") (pintype "passive"))
    )
    (net (code "190") (name "Net-(Q5-C)") (class "Default")
      (node (ref "Q5") (pin "3") (pinfunction "C_3") (pintype "passive"))
      (node (ref "R75") (pin "1") (pinfunction "1_1") (pintype "passive"))
    )
    (net (code "191") (name "Net-(Q6-C)") (class "Default")
      (node (ref "Q6") (pin "3") (pinfunction "C_3") (pintype "passive"))
      (node (ref "R47") (pin "2") (pinfunction "2_2") (pintype "passive"))
    )
    (net (code "192") (name "Net-(Q7-C)") (class "Default")
      (node (ref "Q7") (pin "3") (pinfunction "C_3") (pintype "passive"))
      (node (ref "R84") (pin "1") (pinfunction "1_1") (pintype "passive"))
    )
    (net (code "193") (name "Net-(Q8-C)") (class "Default")
      (node (ref "Q8") (pin "3") (pinfunction "C_3") (pintype "passive"))
      (node (ref "R102") (pin "2") (pinfunction "2_2") (pintype "passive"))
    )
    (net (code "194") (name "Net-(Q9-C)") (class "Default")
      (node (ref "Q9") (pin "3") (pinfunction "C_3") (pintype "passive"))
      (node (ref "R58") (pin "1") (pinfunction "1_1") (pintype "passive"))
    )
    (net (code "195") (name "Net-(Q10-C)") (class "Default")
      (node (ref "Q10") (pin "3") (pinfunction "C_3") (pintype "passive"))
      (node (ref "R38") (pin "2") (pinfunction "2_2") (pintype "passive"))
    )
    (net (code "196") (name "Net-(Q11-C)") (class "Default")
      (node (ref "Q11") (pin "3") (pinfunction "C_3") (pintype "passive"))
      (node (ref "R67") (pin "1") (pinfunction "1_1") (pintype "passive"))
    )
    (net (code "197") (name "Net-(Q12-C)") (class "Default")
      (node (ref "Q12") (pin "3") (pinfunction "C_3") (pintype "passive"))
      (node (ref "R94") (pin "2") (pinfunction "2_2") (pintype "passive"))
    )
    (net (code "198") (name "Net-(Q13-C)") (class "Default")
      (node (ref "Q13") (pin "3") (pinfunction "C_3") (pintype "passive"))
      (node (ref "R76") (pin "1") (pinfunction "1_1") (pintype "passive"))
    )
    (net (code "199") (name "Net-(Q14-C)") (class "Default")
      (node (ref "Q14") (pin "3") (pinfunction "C_3") (pintype "passive"))
      (node (ref "R48") (pin "2") (pinfunction "2_2") (pintype "passive"))
    )
    (net (code "200") (name "Net-(Q15-C)") (class "Default")
      (node (ref "Q15") (pin "3") (pinfunction "C_3") (pintype "passive"))
      (node (ref "R85") (pin "1") (pinfunction "1_1") (pintype "passive"))
    )
    (net (code "201") (name "Net-(Q16-C)") (class "Default")
      (node (ref "Q16") (pin "3") (pinfunction "C_3") (pintype "passive"))
      (node (ref "R103") (pin "2") (pinfunction "2_2") (pintype "passive"))
    )
    (net (code "202") (name "Net-(Q17-C)") (class "Default")
      (node (ref "Q17") (pin "3") (pinfunction "C_3") (pintype "passive"))
      (node (ref "R59") (pin "1") (pinfunction "1_1") (pintype "passive"))
    )
    (net (code "203") (name "Net-(Q18-C)") (class "Default")
      (node (ref "Q18") (pin "3") (pinfunction "C_3") (pintype "passive"))
      (node (ref "R40") (pin "2") (pinfunction "2_2") (pintype "passive"))
    )
    (net (code "204") (name "Net-(Q19-C)") (class "Default")
      (node (ref "Q19") (pin "3") (pinfunction "C_3") (pintype "passive"))
      (node (ref "R68") (pin "1") (pinfunction "1_1") (pintype "passive"))
    )
    (net (code "205") (name "Net-(Q20-C)") (class "Default")
      (node (ref "Q20") (pin "3") (pinfunction "C_3") (pintype "passive"))
      (node (ref "R95") (pin "2") (pinfunction "2_2") (pintype "passive"))
    )
    (net (code "206") (name "Net-(Q21-C)") (class "Default")
      (node (ref "Q21") (pin "3") (pinfunction "C_3") (pintype "passive"))
      (node (ref "R77") (pin "1") (pinfunction "1_1") (pintype "passive"))
    )
    (net (code "207") (name "Net-(Q22-C)") (class "Default")
      (node (ref "Q22") (pin "3") (pinfunction "C_3") (pintype "passive"))
      (node (ref "R49") (pin "2") (pinfunction "2_2") (pintype "passive"))
    )
    (net (code "208") (name "Net-(Q23-C)") (class "Default")
      (node (ref "Q23") (pin "3") (pinfunction "C_3") (pintype "passive"))
      (node (ref "R86") (pin "1") (pinfunction "1_1") (pintype "passive"))
    )
    (net (code "209") (name "Net-(Q24-C)") (class "Default")
      (node (ref "Q24") (pin "3") (pinfunction "C_3") (pintype "passive"))
      (node (ref "R104") (pin "2") (pinfunction "2_2") (pintype "passive"))
    )
    (net (code "210") (name "Net-(Q25-C)") (class "Default")
      (node (ref "Q25") (pin "3") (pinfunction "C_3") (pintype "passive"))
      (node (ref "R60") (pin "1") (pinfunction "1_1") (pintype "passive"))
    )
    (net (code "211") (name "Net-(Q26-C)") (class "Default")
      (node (ref "Q26") (pin "3") (pinfunction "C_3") (pintype "passive"))
      (node (ref "R41") (pin "2") (pinfunction "2_2") (pintype "passive"))
    )
    (net (code "212") (name "Net-(Q27-C)") (class "Default")
      (node (ref "Q27") (pin "3") (pinfunction "C_3") (pintype "passive"))
      (node (ref "R69") (pin "1") (pinfunction "1_1") (pintype "passive"))
    )
    (net (code "213") (name "Net-(Q28-C)") (class "Default")
      (node (ref "Q28") (pin "3") (pinfunction "C_3") (pintype "passive"))
      (node (ref "R96") (pin "2") (pinfunction "2_2") (pintype "passive"))
    )
    (net (code "214") (name "Net-(Q29-C)") (class "Default")
      (node (ref "Q29") (pin "3") (pinfunction "C_3") (pintype "passive"))
      (node (ref "R78") (pin "1") (pinfunction "1_1") (pintype "passive"))
    )
    (net (code "215") (name "Net-(Q30-C)") (class "Default")
      (node (ref "Q30") (pin "3") (pinfunction "C_3") (pintype "passive"))
      (node (ref "R50") (pin "2") (pinfunction "2_2") (pintype "passive"))
    )
    (net (code "216") (name "Net-(Q31-C)") (class "Default")
      (node (ref "Q31") (pin "3") (pinfunction "C_3") (pintype "passive"))
      (node (ref "R87") (pin "1") (pinfunction "1_1") (pintype "passive"))
    )
    (net (code "217") (name "Net-(Q32-C)") (class "Default")
      (node (ref "Q32") (pin "3") (pinfunction "C_3") (pintype "passive"))
      (node (ref "R105") (pin "2") (pinfunction "2_2") (pintype "passive"))
    )
    (net (code "218") (name "Net-(Q33-C)") (class "Default")
      (node (ref "Q33") (pin "3") (pinfunction "C_3") (pintype "passive"))
      (node (ref "R61") (pin "1") (pinfunction "1_1") (pintype "passive"))
    )
    (net (code "219") (name "Net-(Q34-C)") (class "Default")
      (node (ref "Q34") (pin "3") (pinfunction "C_3") (pintype "passive"))
      (node (ref "R42") (pin "2") (pinfunction "2_2") (pintype "passive"))
    )
    (net (code "220") (name "Net-(Q35-C)") (class "Default")
      (node (ref "Q35") (pin "3") (pinfunction "C_3") (pintype "passive"))
      (node (ref "R70") (pin "1") (pinfunction "1_1") (pintype "passive"))
    )
    (net (code "221") (name "Net-(Q36-C)") (class "Default")
      (node (ref "Q36") (pin "3") (pinfunction "C_3") (pintype "passive"))
      (node (ref "R97") (pin "2") (pinfunction "2_2") (pintype "passive"))
    )
    (net (code "222") (name "Net-(Q37-C)") (class "Default")
      (node (ref "Q37") (pin "3") (pinfunction "C_3") (pintype "passive"))
      (node (ref "R79") (pin "1") (pinfunction "1_1") (pintype "passive"))
    )
    (net (code "223") (name "Net-(Q38-C)") (class "Default")
      (node (ref "Q38") (pin "3") (pinfunction "C_3") (pintype "passive"))
      (node (ref "R51") (pin "2") (pinfunction "2_2") (pintype "passive"))
    )
    (net (code "224") (name "Net-(Q39-C)") (class "Default")
      (node (ref "Q39") (pin "3") (pinfunction "C_3") (pintype "passive"))
      (node (ref "R88") (pin "1") (pinfunction "1_1") (pintype "passive"))
    )
    (net (code "225") (name "Net-(Q40-C)") (class "Default")
      (node (ref "Q40") (pin "3") (pinfunction "C_3") (pintype "passive"))
      (node (ref "R106") (pin "2") (pinfunction "2_2") (pintype "passive"))
    )
    (net (code "226") (name "Net-(Q41-C)") (class "Default")
      (node (ref "Q41") (pin "3") (pinfunction "C_3") (pintype "passive"))
      (node (ref "R62") (pin "1") (pinfunction "1_1") (pintype "passive"))
    )
    (net (code "227") (name "Net-(Q42-C)") (class "Default")
      (node (ref "Q42") (pin "3") (pinfunction "C_3") (pintype "passive"))
      (node (ref "R43") (pin "2") (pinfunction "2_2") (pintype "passive"))
    )
    (net (code "228") (name "Net-(Q43-C)") (class "Default")
      (node (ref "Q43") (pin "3") (pinfunction "C_3") (pintype "passive"))
      (node (ref "R71") (pin "1") (pinfunction "1_1") (pintype "passive"))
    )
    (net (code "229") (name "Net-(Q44-C)") (class "Default")
      (node (ref "Q44") (pin "3") (pinfunction "C_3") (pintype "passive"))
      (node (ref "R98") (pin "2") (pinfunction "2_2") (pintype "passive"))
    )
    (net (code "230") (name "Net-(Q45-C)") (class "Default")
      (node (ref "Q45") (pin "3") (pinfunction "C_3") (pintype "passive"))
      (node (ref "R80") (pin "1") (pinfunction "1_1") (pintype "passive"))
    )
    (net (code "231") (name "Net-(Q46-C)") (class "Default")
      (node (ref "Q46") (pin "3") (pinfunction "C_3") (pintype "passive"))
      (node (ref "R52") (pin "2") (pinfunction "2_2") (pintype "passive"))
    )
    (net (code "232") (name "Net-(Q47-C)") (class "Default")
      (node (ref "Q47") (pin "3") (pinfunction "C_3") (pintype "passive"))
      (node (ref "R89") (pin "1") (pinfunction "1_1") (pintype "passive"))
    )
    (net (code "233") (name "Net-(Q48-C)") (class "Default")
      (node (ref "Q48") (pin "3") (pinfunction "C_3") (pintype "passive"))
      (node (ref "R107") (pin "2") (pinfunction "2_2") (pintype "passive"))
    )
    (net (code "234") (name "Net-(Q49-C)") (class "Default")
      (node (ref "Q49") (pin "3") (pinfunction "C_3") (pintype "passive"))
      (node (ref "R63") (pin "1") (pinfunction "1_1") (pintype "passive"))
    )
    (net (code "235") (name "Net-(Q50-C)") (class "Default")
      (node (ref "Q50") (pin "3") (pinfunction "C_3") (pintype "passive"))
      (node (ref "R44") (pin "2") (pinfunction "2_2") (pintype "passive"))
    )
    (net (code "236") (name "Net-(Q51-C)") (class "Default")
      (node (ref "Q51") (pin "3") (pinfunction "C_3") (pintype "passive"))
      (node (ref "R72") (pin "1") (pinfunction "1_1") (pintype "passive"))
    )
    (net (code "237") (name "Net-(Q52-C)") (class "Default")
      (node (ref "Q52") (pin "3") (pinfunction "C_3") (pintype "passive"))
      (node (ref "R99") (pin "2") (pinfunction "2_2") (pintype "passive"))
    )
    (net (code "238") (name "Net-(Q53-C)") (class "Default")
      (node (ref "Q53") (pin "3") (pinfunction "C_3") (pintype "passive"))
      (node (ref "R81") (pin "1") (pinfunction "1_1") (pintype "passive"))
    )
    (net (code "239") (name "Net-(Q54-C)") (class "Default")
      (node (ref "Q54") (pin "3") (pinfunction "C_3") (pintype "passive"))
      (node (ref "R53") (pin "2") (pinfunction "2_2") (pintype "passive"))
    )
    (net (code "240") (name "Net-(Q55-C)") (class "Default")
      (node (ref "Q55") (pin "3") (pinfunction "C_3") (pintype "passive"))
      (node (ref "R90") (pin "1") (pinfunction "1_1") (pintype "passive"))
    )
    (net (code "241") (name "Net-(Q56-C)") (class "Default")
      (node (ref "Q56") (pin "3") (pinfunction "C_3") (pintype "passive"))
      (node (ref "R108") (pin "2") (pinfunction "2_2") (pintype "passive"))
    )
    (net (code "242") (name "Net-(Q57-C)") (class "Default")
      (node (ref "Q57") (pin "3") (pinfunction "C_3") (pintype "passive"))
      (node (ref "R64") (pin "1") (pinfunction "1_1") (pintype "passive"))
    )
    (net (code "243") (name "Net-(Q58-C)") (class "Default")
      (node (ref "Q58") (pin "3") (pinfunction "C_3") (pintype "passive"))
      (node (ref "R45") (pin "2") (pinfunction "2_2") (pintype "passive"))
    )
    (net (code "244") (name "Net-(Q59-C)") (class "Default")
      (node (ref "Q59") (pin "3") (pinfunction "C_3") (pintype "passive"))
      (node (ref "R73") (pin "1") (pinfunction "1_1") (pintype "passive"))
    )
    (net (code "245") (name "Net-(Q60-C)") (class "Default")
      (node (ref "Q60") (pin "3") (pinfunction "C_3") (pintype "passive"))
      (node (ref "R100") (pin "2") (pinfunction "2_2") (pintype "passive"))
    )
    (net (code "246") (name "Net-(Q61-C)") (class "Default")
      (node (ref "Q61") (pin "3") (pinfunction "C_3") (pintype "passive"))
      (node (ref "R82") (pin "1") (pinfunction "1_1") (pintype "passive"))
    )
    (net (code "247") (name "Net-(Q62-C)") (class "Default")
      (node (ref "Q62") (pin "3") (pinfunction "C_3") (pintype "passive"))
      (node (ref "R54") (pin "2") (pinfunction "2_2") (pintype "passive"))
    )
    (net (code "248") (name "Net-(Q63-C)") (class "Default")
      (node (ref "Q63") (pin "3") (pinfunction "C_3") (pintype "passive"))
      (node (ref "R91") (pin "1") (pinfunction "1_1") (pintype "passive"))
    )
    (net (code "249") (name "Net-(Q64-C)") (class "Default")
      (node (ref "Q64") (pin "3") (pinfunction "C_3") (pintype "passive"))
      (node (ref "R109") (pin "2") (pinfunction "2_2") (pintype "passive"))
    )
    (net (code "250") (name "Net-(Q65-C)") (class "Default")
      (node (ref "Q65") (pin "3") (pinfunction "C_3") (pintype "passive"))
      (node (ref "R65") (pin "1") (pinfunction "1_1") (pintype "passive"))
    )
    (net (code "251") (name "Net-(Q66-C)") (class "Default")
      (node (ref "Q66") (pin "3") (pinfunction "C_3") (pintype "passive"))
      (node (ref "R46") (pin "2") (pinfunction "2_2") (pintype "passive"))
    )
    (net (code "252") (name "Net-(Q67-C)") (class "Default")
      (node (ref "Q67") (pin "3") (pinfunction "C_3") (pintype "passive"))
      (node (ref "R74") (pin "1") (pinfunction "1_1") (pintype "passive"))
    )
    (net (code "253") (name "Net-(Q68-C)") (class "Default")
      (node (ref "Q68") (pin "3") (pinfunction "C_3") (pintype "passive"))
      (node (ref "R101") (pin "2") (pinfunction "2_2") (pintype "passive"))
    )
    (net (code "254") (name "Net-(Q69-C)") (class "Default")
      (node (ref "Q69") (pin "3") (pinfunction "C_3") (pintype "passive"))
      (node (ref "R83") (pin "1") (pinfunction "1_1") (pintype "passive"))
    )
    (net (code "255") (name "Net-(Q70-C)") (class "Default")
      (node (ref "Q70") (pin "3") (pinfunction "C_3") (pintype "passive"))
      (node (ref "R55") (pin "2") (pinfunction "2_2") (pintype "passive"))
    )
    (net (code "256") (name "Net-(Q71-C)") (class "Default")
      (node (ref "Q71") (pin "3") (pinfunction "C_3") (pintype "passive"))
      (node (ref "R92") (pin "1") (pinfunction "1_1") (pintype "passive"))
    )
    (net (code "257") (name "Net-(Q72-C)") (class "Default")
      (node (ref "Q72") (pin "3") (pinfunction "C_3") (pintype "passive"))
      (node (ref "R110") (pin "2") (pinfunction "2_2") (pintype "passive"))
    )
    (net (code "258") (name "VCC") (class "Default")
      (node (ref "R57") (pin "2") (pinfunction "2_2") (pintype "passive"))
      (node (ref "R58") (pin "2") (pinfunction "2_2") (pintype "passive"))
      (node (ref "R59") (pin "2") (pinfunction "2_2") (pintype "passive"))
      (node (ref "R60") (pin "2") (pinfunction "2_2") (pintype "passive"))
      (node (ref "R61") (pin "2") (pinfunction "2_2") (pintype "passive"))
      (node (ref "R62") (pin "2") (pinfunction "2_2") (pintype "passive"))
      (node (ref "R63") (pin "2") (pinfunction "2_2") (pintype "passive"))
      (node (ref "R64") (pin "2") (pinfunction "2_2") (pintype "passive"))
      (node (ref "R65") (pin "2") (pinfunction "2_2") (pintype "passive"))
      (node (ref "R66") (pin "2") (pinfunction "2_2") (pintype "passive"))
      (node (ref "R67") (pin "2") (pinfunction "2_2") (pintype "passive"))
      (node (ref "R68") (pin "2") (pinfunction "2_2") (pintype "passive"))
      (node (ref "R69") (pin "2") (pinfunction "2_2") (pintype "passive"))
      (node (ref "R70") (pin "2") (pinfunction "2_2") (pintype "passive"))
      (node (ref "R71") (pin "2") (pinfunction "2_2") (pintype "passive"))
      (node (ref "R72") (pin "2") (pinfunction "2_2") (pintype "passive"))
      (node (ref "R73") (pin "2") (pinfunction "2_2") (pintype "passive"))
      (node (ref "R74") (pin "2") (pinfunction "2_2") (pintype "passive"))
      (node (ref "R75") (pin "2") (pinfunction "2_2") (pintype "passive"))
      (node (ref "R76") (pin "2") (pinfunction "2_2") (pintype "passive"))
      (node (ref "R77") (pin "2") (pinfunction "2_2") (pintype "passive"))
      (node (ref "R78") (pin "2") (pinfunction "2_2") (pintype "passive"))
      (node (ref "R79") (pin "2") (pinfunction "2_2") (pintype "passive"))
      (node (ref "R80") (pin "2") (pinfunction "2_2") (pintype "passive"))
      (node (ref "R81") (pin "2") (pinfunction "2_2") (pintype "passive"))
      (node (ref "R82") (pin "2") (pinfunction "2_2") (pintype "passive"))
      (node (ref "R83") (pin "2") (pinfunction "2_2") (pintype "passive"))
      (node (ref "R84") (pin "2") (pinfunction "2_2") (pintype "passive"))
      (node (ref "R85") (pin "2") (pinfunction "2_2") (pintype "passive"))
      (node (ref "R86") (pin "2") (pinfunction "2_2") (pintype "passive"))
      (node (ref "R87") (pin "2") (pinfunction "2_2") (pintype "passive"))
      (node (ref "R88") (pin "2") (pinfunction "2_2") (pintype "passive"))
      (node (ref "R89") (pin "2") (pinfunction "2_2") (pintype "passive"))
      (node (ref "R90") (pin "2") (pinfunction "2_2") (pintype "passive"))
      (node (ref "R91") (pin "2") (pinfunction "2_2") (pintype "passive"))
      (node (ref "R92") (pin "2") (pinfunction "2_2") (pintype "passive"))
    )
    (net (code "259") (name "VSS") (class "Default")
      (node (ref "R100") (pin "1") (pinfunction "1_1") (pintype "passive"))
      (node (ref "R101") (pin "1") (pinfunction "1_1") (pintype "passive"))
      (node (ref "R102") (pin "1") (pinfunction "1_1") (pintype "passive"))
      (node (ref "R103") (pin "1") (pinfunction "1_1") (pintype "passive"))
      (node (ref "R104") (pin "1") (pinfunction "1_1") (pintype "passive"))
      (node (ref "R105") (pin "1") (pinfunction "1_1") (pintype "passive"))
      (node (ref "R106") (pin "1") (pinfunction "1_1") (pintype "passive"))
      (node (ref "R107") (pin "1") (pinfunction "1_1") (pintype "passive"))
      (node (ref "R108") (pin "1") (pinfunction "1_1") (pintype "passive"))
      (node (ref "R109") (pin "1") (pinfunction "1_1") (pintype "passive"))
      (node (ref "R110") (pin "1") (pinfunction "1_1") (pintype "passive"))
      (node (ref "R38") (pin "1") (pinfunction "1_1") (pintype "passive"))
      (node (ref "R39") (pin "1") (pinfunction "1_1") (pintype "passive"))
      (node (ref "R40") (pin "1") (pinfunction "1_1") (pintype "passive"))
      (node (ref "R41") (pin "1") (pinfunction "1_1") (pintype "passive"))
      (node (ref "R42") (pin "1") (pinfunction "1_1") (pintype "passive"))
      (node (ref "R43") (pin "1") (pinfunction "1_1") (pintype "passive"))
      (node (ref "R44") (pin "1") (pinfunction "1_1") (pintype "passive"))
      (node (ref "R45") (pin "1") (pinfunction "1_1") (pintype "passive"))
      (node (ref "R46") (pin "1") (pinfunction "1_1") (pintype "passive"))
      (node (ref "R47") (pin "1") (pinfunction "1_1") (pintype "passive"))
      (node (ref "R48") (pin "1") (pinfunction "1_1") (pintype "passive"))
      (node (ref "R49") (pin "1") (pinfunction "1_1") (pintype "passive"))
      (node (ref "R50") (pin "1") (pinfunction "1_1") (pintype "passive"))
      (node (ref "R51") (pin "1") (pinfunction "1_1") (pintype "passive"))
      (node (ref "R52") (pin "1") (pinfunction "1_1") (pintype "passive"))
      (node (ref "R53") (pin "1") (pinfunction "1_1") (pintype "passive"))
      (node (ref "R54") (pin "1") (pinfunction "1_1") (pintype "passive"))
      (node (ref "R55") (pin "1") (pinfunction "1_1") (pintype "passive"))
      (node (ref "R93") (pin "1") (pinfunction "1_1") (pintype "passive"))
      (node (ref "R94") (pin "1") (pinfunction "1_1") (pintype "passive"))
      (node (ref "R95") (pin "1") (pinfunction "1_1") (pintype "passive"))
      (node (ref "R96") (pin "1") (pinfunction "1_1") (pintype "passive"))
      (node (ref "R97") (pin "1") (pinfunction "1_1") (pintype "passive"))
      (node (ref "R98") (pin "1") (pinfunction "1_1") (pintype "passive"))
      (node (ref "R99") (pin "1") (pinfunction "1_1") (pintype "passive"))
    )
  )
)
